# STGHW00054_A2.net
KiCad netlist of a schematic drawn in EAGLE
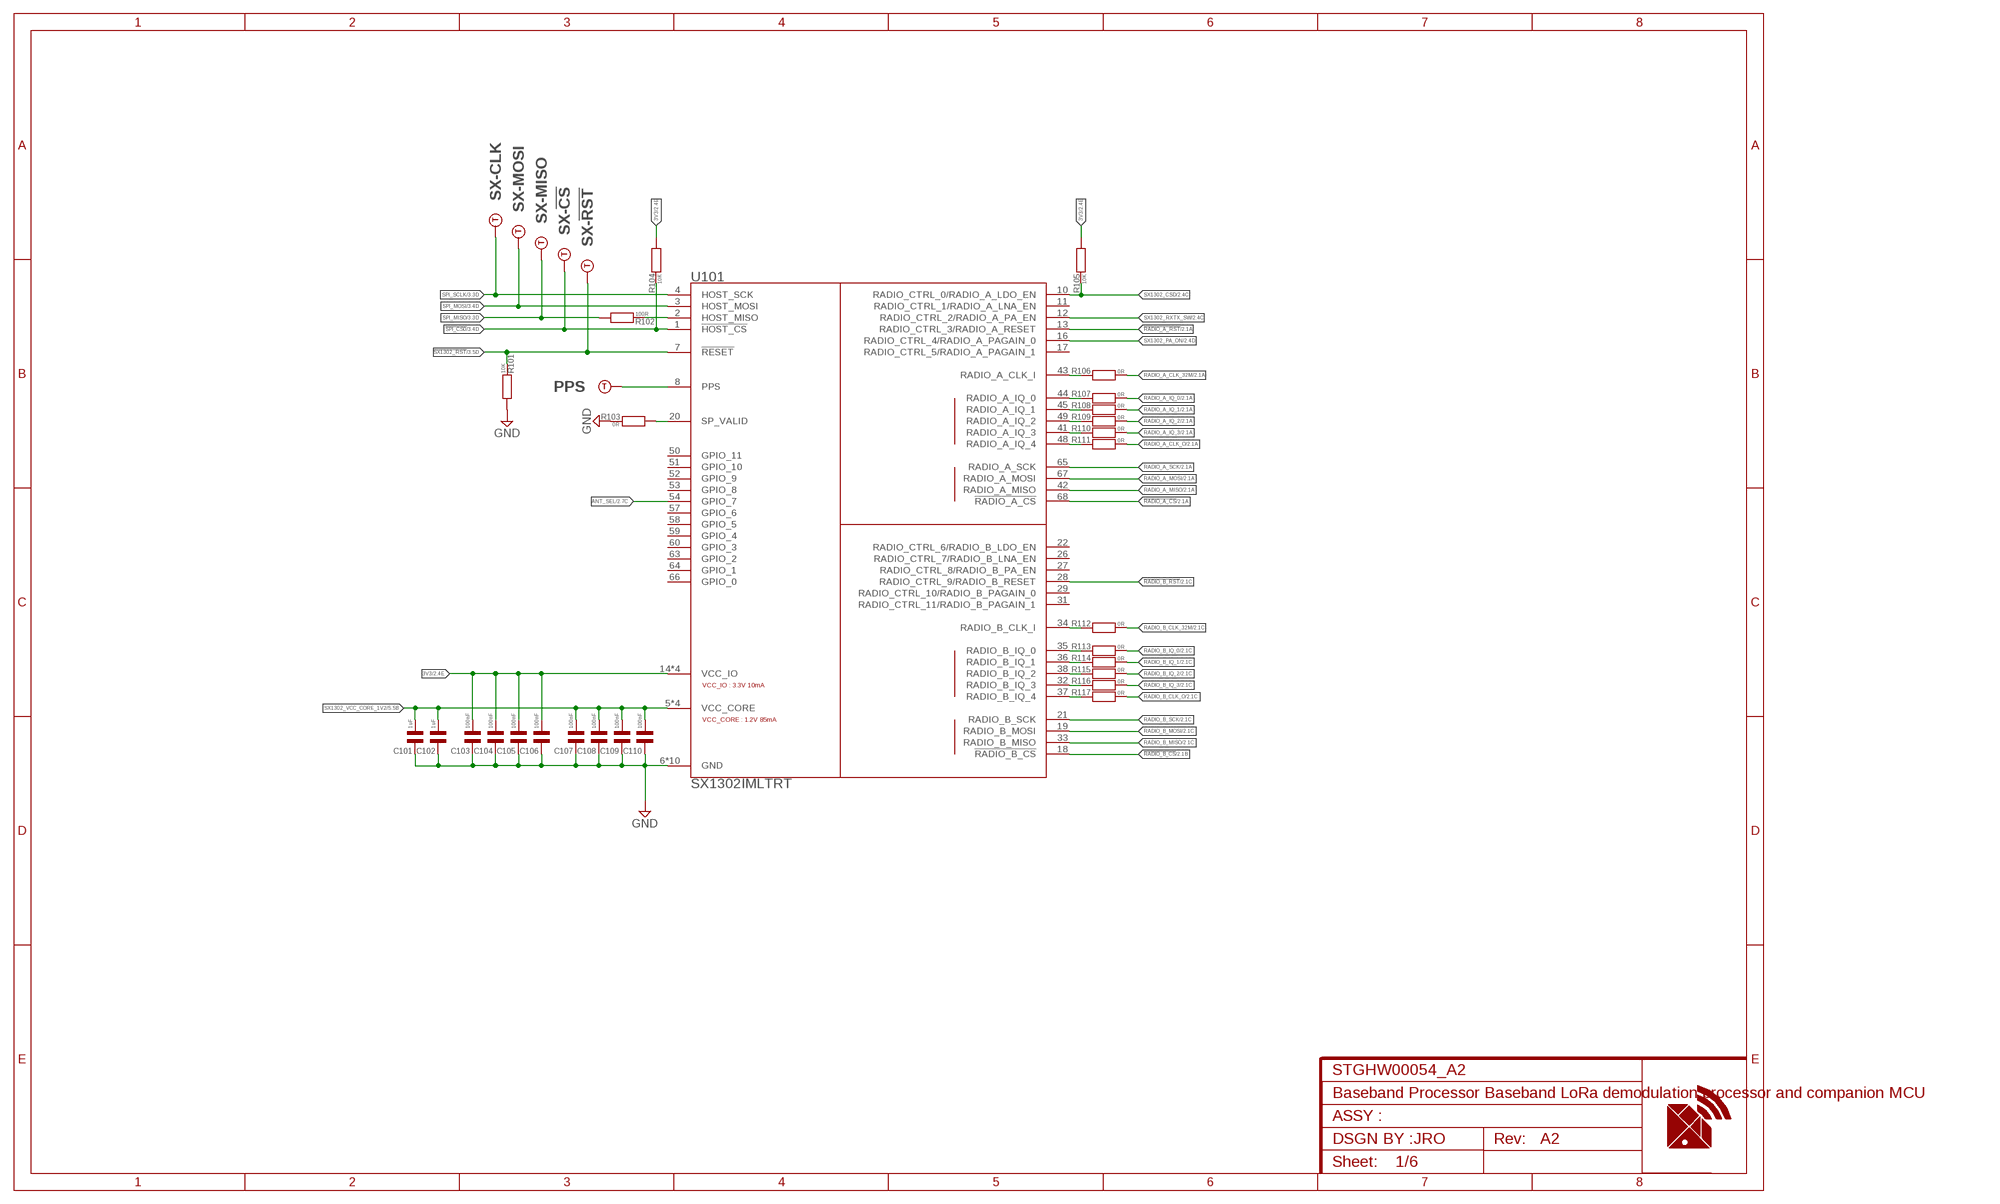
[diagram p0: schematic, sheet 1]
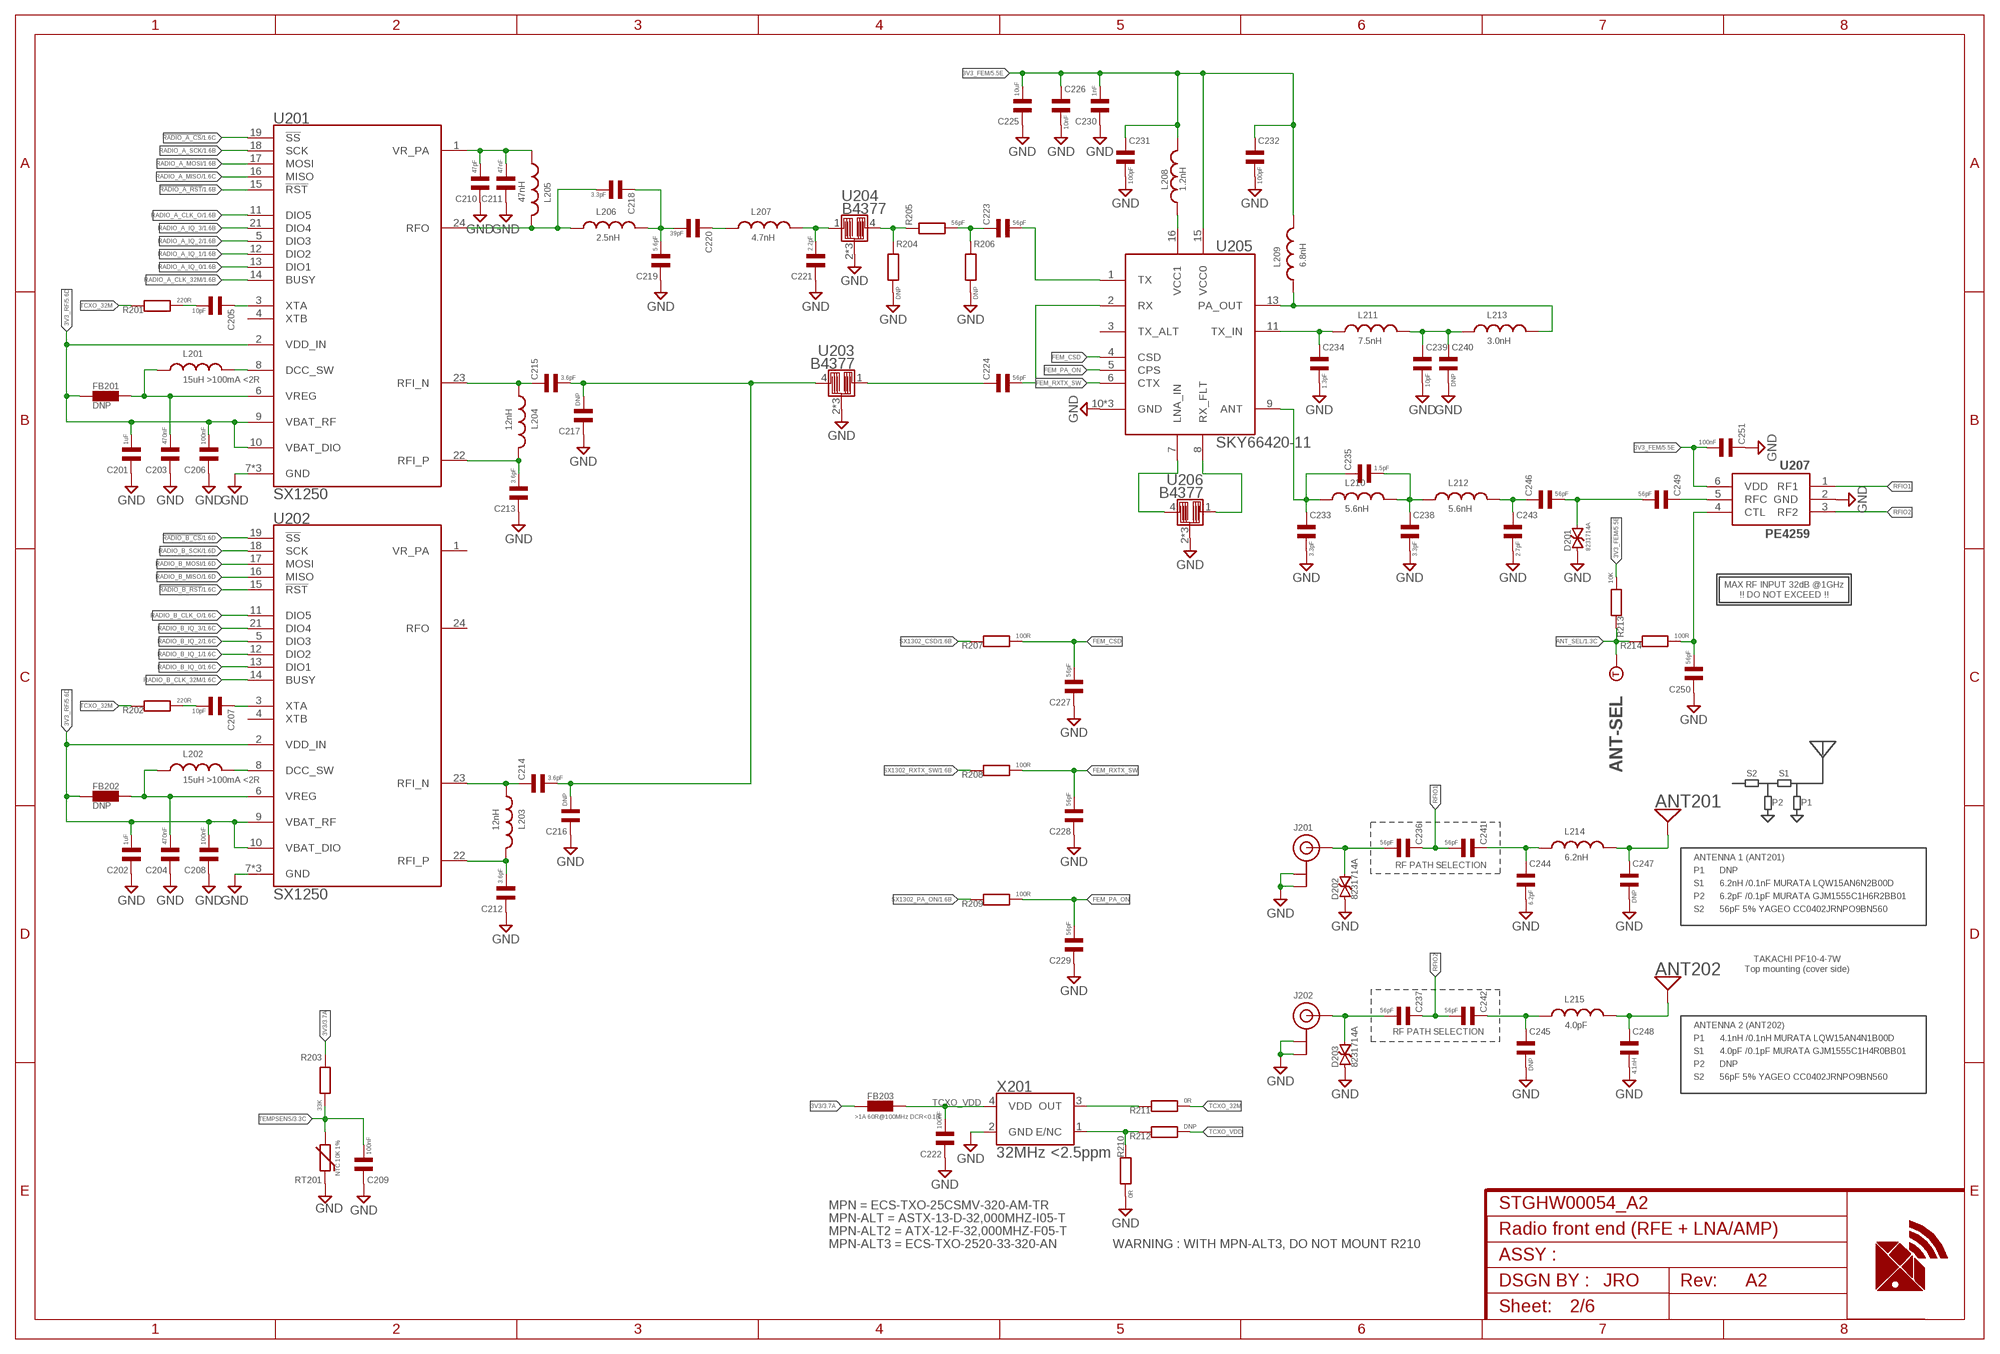
[diagram p1: schematic, sheet 2]
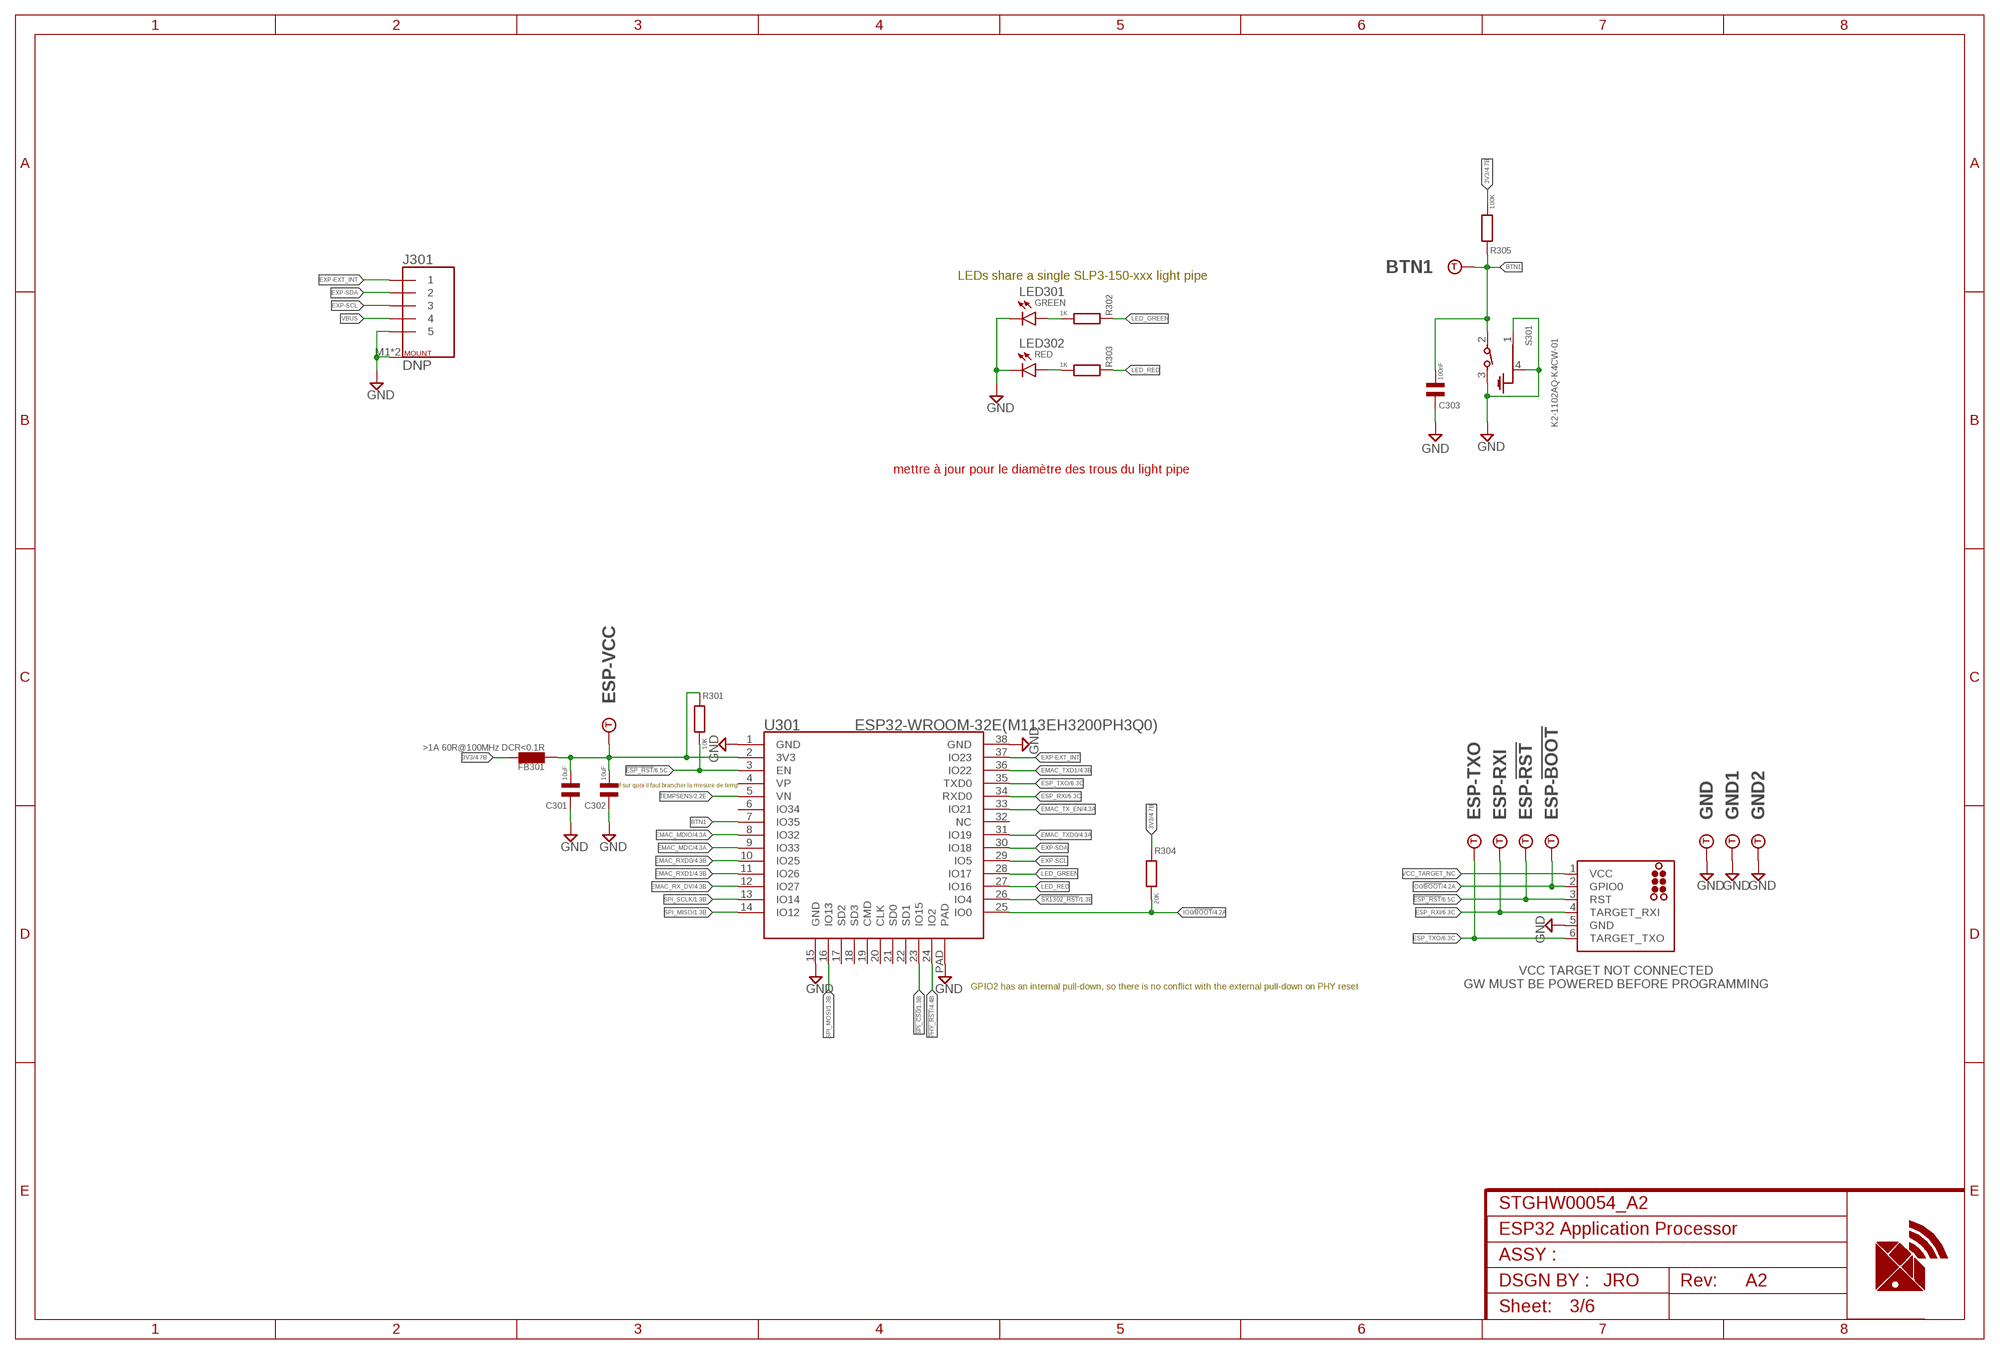
[diagram p2: schematic, sheet 3]
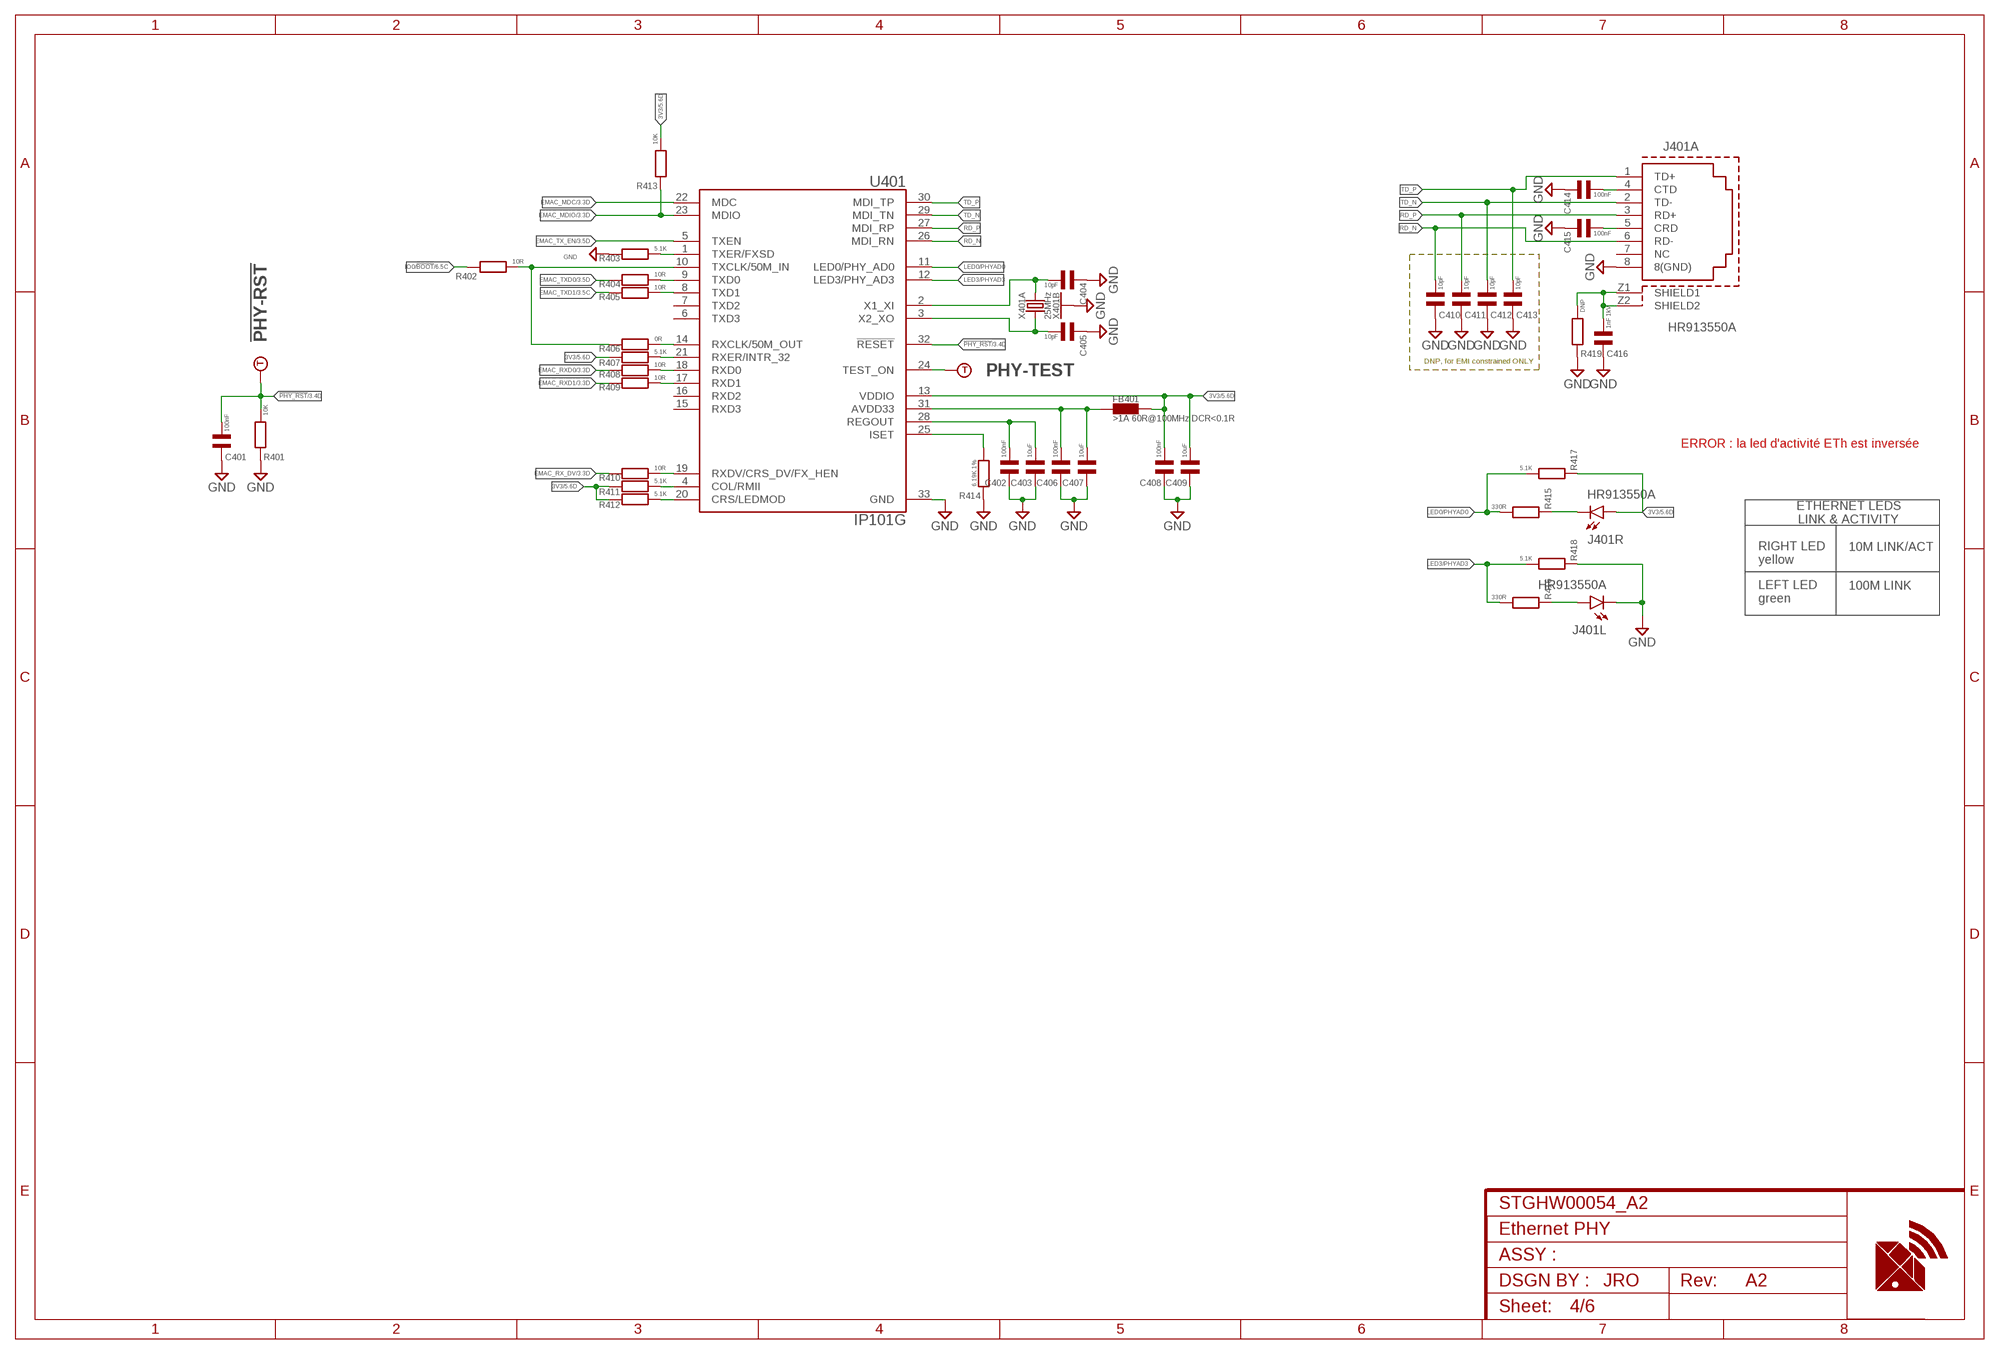
[diagram p3: schematic, sheet 4]
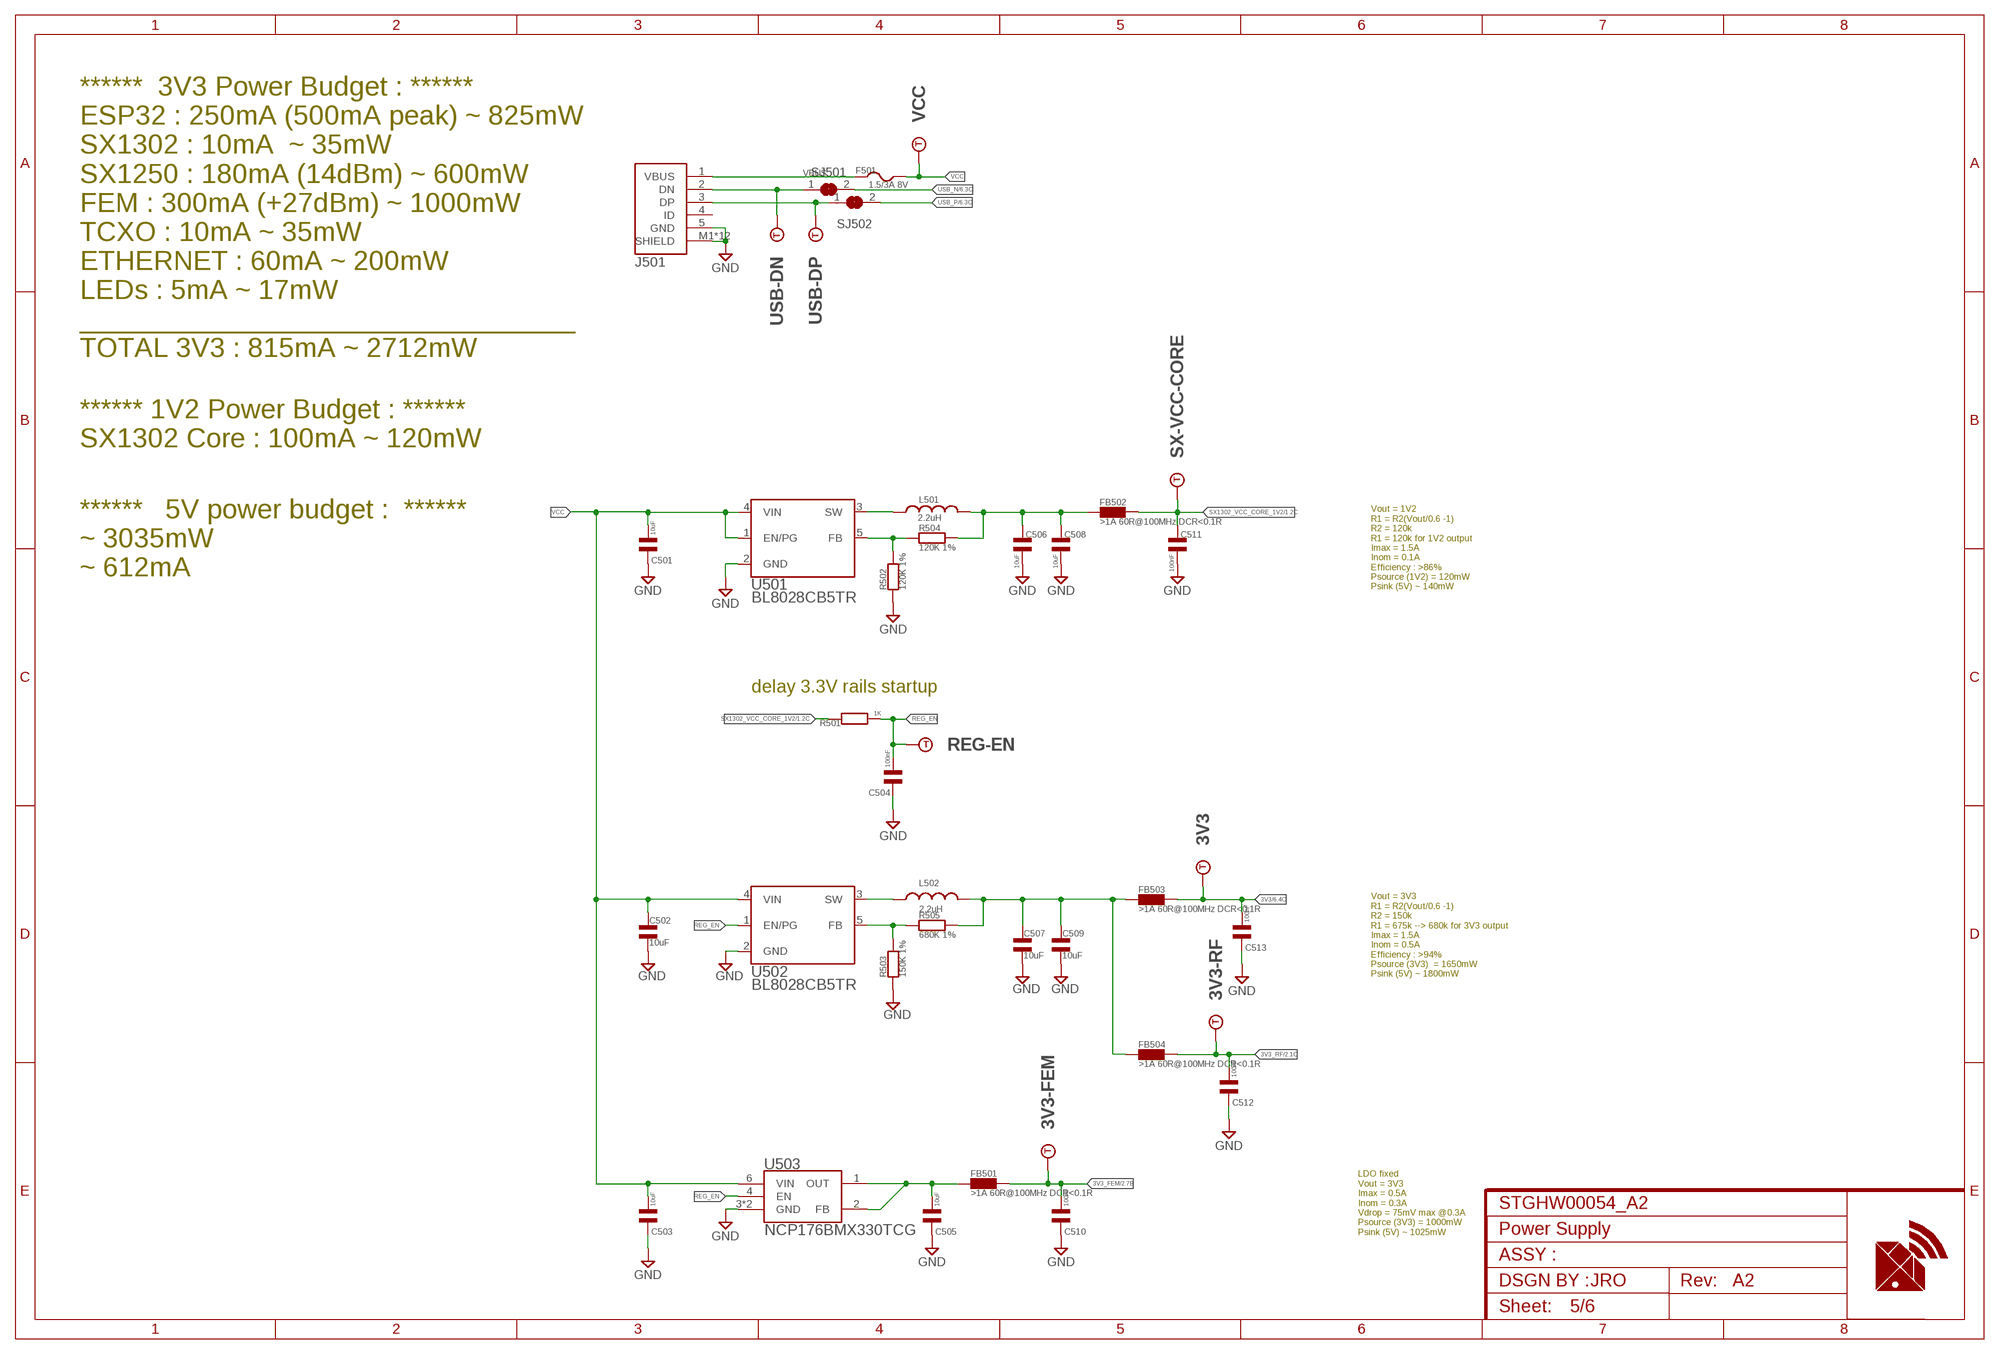
[diagram p4: schematic, sheet 5]
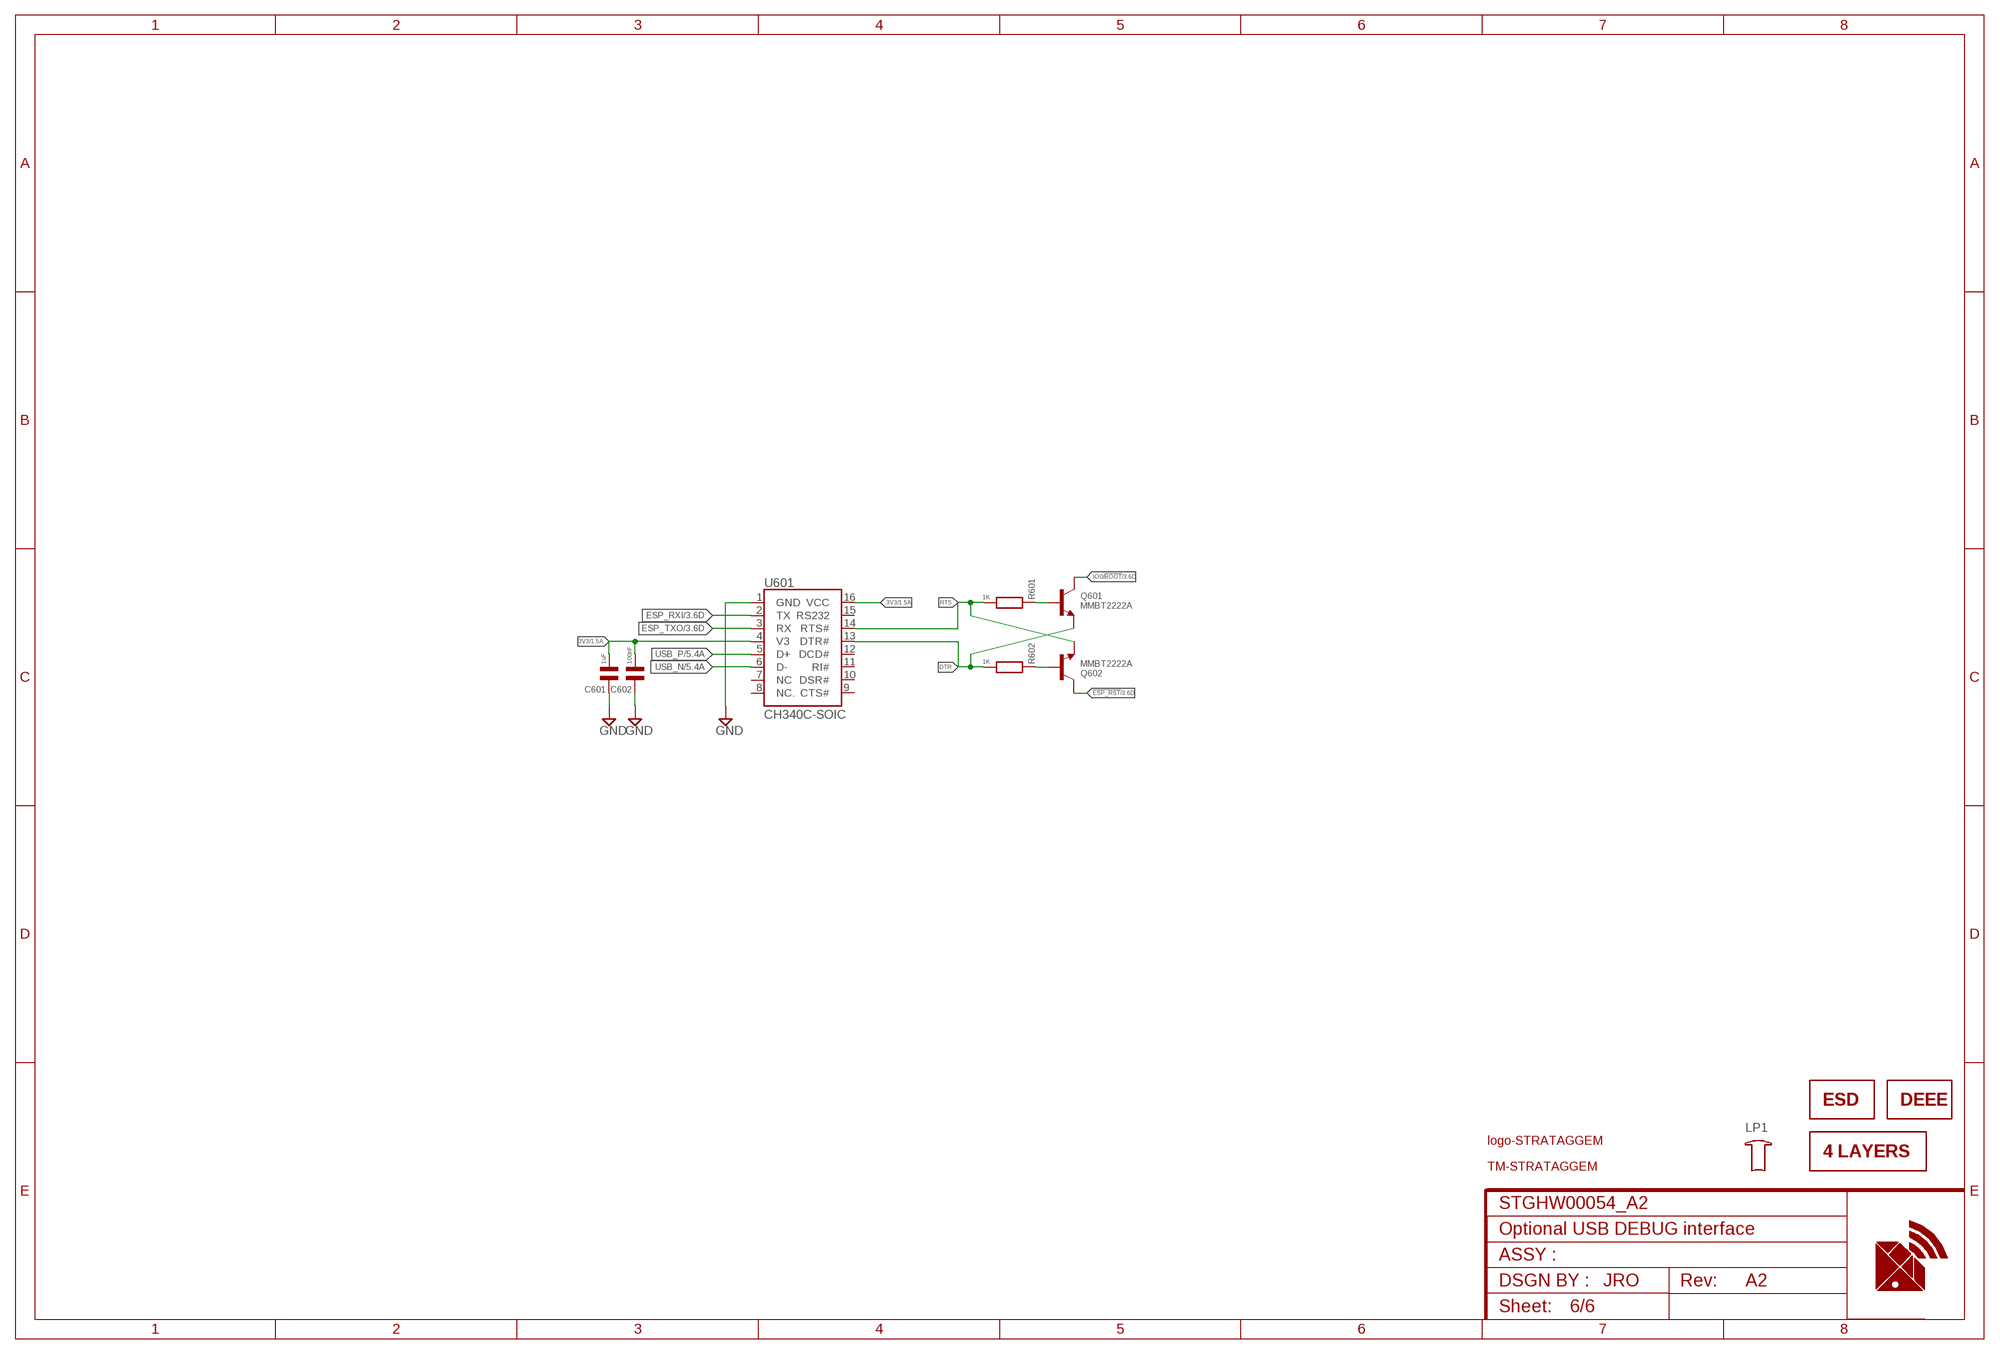
[diagram p5: schematic, sheet 6]

(export (version "E")
  (design (tool "Eeschema 10.0.6"))
  (components
    (comp (ref "C101")
      (value "1uF")
      (footprint "eagle-import:C0402")
      (fields (field (name "MPN") "CL05A105KO5NNNC"))
      (libsource (lib "eagle-import") (part "CAPACITOR-NP-0402"))
    )
    (comp (ref "C102")
      (value "1uF")
      (footprint "eagle-import:C0402")
      (fields (field (name "MPN") "CL05A105KO5NNNC"))
      (libsource (lib "eagle-import") (part "CAPACITOR-NP-0402"))
    )
    (comp (ref "C103")
      (value "100nF")
      (footprint "eagle-import:C0402")
      (fields (field (name "MPN") "CC0402KRX7R7BB104"))
      (libsource (lib "eagle-import") (part "CAPACITOR-NP-0402"))
    )
    (comp (ref "C104")
      (value "100nF")
      (footprint "eagle-import:C0402")
      (fields (field (name "MPN") "CC0402KRX7R7BB104"))
      (libsource (lib "eagle-import") (part "CAPACITOR-NP-0402"))
    )
    (comp (ref "C105")
      (value "100nF")
      (footprint "eagle-import:C0402")
      (fields (field (name "MPN") "CC0402KRX7R7BB104"))
      (libsource (lib "eagle-import") (part "CAPACITOR-NP-0402"))
    )
    (comp (ref "C106")
      (value "100nF")
      (footprint "eagle-import:C0402")
      (fields (field (name "MPN") "CC0402KRX7R7BB104"))
      (libsource (lib "eagle-import") (part "CAPACITOR-NP-0402"))
    )
    (comp (ref "C107")
      (value "100nF")
      (footprint "eagle-import:C0402")
      (fields (field (name "MPN") "CC0402KRX7R7BB104"))
      (libsource (lib "eagle-import") (part "CAPACITOR-NP-0402"))
    )
    (comp (ref "C108")
      (value "100nF")
      (footprint "eagle-import:C0402")
      (fields (field (name "MPN") "CC0402KRX7R7BB104"))
      (libsource (lib "eagle-import") (part "CAPACITOR-NP-0402"))
    )
    (comp (ref "C109")
      (value "100nF")
      (footprint "eagle-import:C0402")
      (fields (field (name "MPN") "CC0402KRX7R7BB104"))
      (libsource (lib "eagle-import") (part "CAPACITOR-NP-0402"))
    )
    (comp (ref "C110")
      (value "100nF")
      (footprint "eagle-import:C0402")
      (fields (field (name "MPN") "CC0402KRX7R7BB104"))
      (libsource (lib "eagle-import") (part "CAPACITOR-NP-0402"))
    )
    (comp (ref "PPS")
      (value "TESPOINT-SMD1.5MM")
      (footprint "eagle-import:TESTPOINT-1.5MM")
      (libsource (lib "eagle-import") (part "TESPOINT-SMD1.5MM"))
    )
    (comp (ref "R101")
      (value "10K")
      (footprint "eagle-import:R0402")
      (fields (field (name "MPN") "RC0402JR-0710KL"))
      (libsource (lib "eagle-import") (part "RESISTOR-0402"))
    )
    (comp (ref "R102")
      (value "100R")
      (footprint "eagle-import:R0402")
      (fields (field (name "MPN") "RC0402JR-07100RL"))
      (libsource (lib "eagle-import") (part "RESISTOR-0402"))
    )
    (comp (ref "R103")
      (value "0R")
      (footprint "eagle-import:R0402")
      (fields (field (name "MPN") "RC0402JR-070RL"))
      (libsource (lib "eagle-import") (part "RESISTOR-0402"))
    )
    (comp (ref "R104")
      (value "10K")
      (footprint "eagle-import:R0402")
      (fields (field (name "MPN") "RC0402JR-0710KL"))
      (libsource (lib "eagle-import") (part "RESISTOR-0402"))
    )
    (comp (ref "R105")
      (value "10K")
      (footprint "eagle-import:R0402")
      (fields (field (name "MPN") "RC0402JR-0710KL"))
      (libsource (lib "eagle-import") (part "RESISTOR-0402"))
    )
    (comp (ref "R106")
      (value "0R")
      (footprint "eagle-import:R0402")
      (fields (field (name "MPN") "RC0402JR-070RL"))
      (libsource (lib "eagle-import") (part "RESISTOR-0402"))
    )
    (comp (ref "R107")
      (value "0R")
      (footprint "eagle-import:R0402")
      (fields (field (name "MPN") "RC0402JR-070RL"))
      (libsource (lib "eagle-import") (part "RESISTOR-0402"))
    )
    (comp (ref "R108")
      (value "0R")
      (footprint "eagle-import:R0402")
      (fields (field (name "MPN") "RC0402JR-070RL"))
      (libsource (lib "eagle-import") (part "RESISTOR-0402"))
    )
    (comp (ref "R109")
      (value "0R")
      (footprint "eagle-import:R0402")
      (fields (field (name "MPN") "RC0402JR-070RL"))
      (libsource (lib "eagle-import") (part "RESISTOR-0402"))
    )
    (comp (ref "R110")
      (value "0R")
      (footprint "eagle-import:R0402")
      (fields (field (name "MPN") "RC0402JR-070RL"))
      (libsource (lib "eagle-import") (part "RESISTOR-0402"))
    )
    (comp (ref "R111")
      (value "0R")
      (footprint "eagle-import:R0402")
      (fields (field (name "MPN") "RC0402JR-070RL"))
      (libsource (lib "eagle-import") (part "RESISTOR-0402"))
    )
    (comp (ref "R112")
      (value "0R")
      (footprint "eagle-import:R0402")
      (fields (field (name "MPN") "RC0402JR-070RL"))
      (libsource (lib "eagle-import") (part "RESISTOR-0402"))
    )
    (comp (ref "R113")
      (value "0R")
      (footprint "eagle-import:R0402")
      (fields (field (name "MPN") "RC0402JR-070RL"))
      (libsource (lib "eagle-import") (part "RESISTOR-0402"))
    )
    (comp (ref "R114")
      (value "0R")
      (footprint "eagle-import:R0402")
      (fields (field (name "MPN") "RC0402JR-070RL"))
      (libsource (lib "eagle-import") (part "RESISTOR-0402"))
    )
    (comp (ref "R115")
      (value "0R")
      (footprint "eagle-import:R0402")
      (fields (field (name "MPN") "RC0402JR-070RL"))
      (libsource (lib "eagle-import") (part "RESISTOR-0402"))
    )
    (comp (ref "R116")
      (value "0R")
      (footprint "eagle-import:R0402")
      (fields (field (name "MPN") "RC0402JR-070RL"))
      (libsource (lib "eagle-import") (part "RESISTOR-0402"))
    )
    (comp (ref "R117")
      (value "0R")
      (footprint "eagle-import:R0402")
      (fields (field (name "MPN") "RC0402JR-070RL"))
      (libsource (lib "eagle-import") (part "RESISTOR-0402"))
    )
    (comp (ref "SX-!CS!")
      (value "TESPOINT-SMD1.5MM")
      (footprint "eagle-import:TESTPOINT-1.5MM")
      (libsource (lib "eagle-import") (part "TESPOINT-SMD1.5MM"))
    )
    (comp (ref "SX-!RST!")
      (value "TESPOINT-SMD1.5MM")
      (footprint "eagle-import:TESTPOINT-1.5MM")
      (libsource (lib "eagle-import") (part "TESPOINT-SMD1.5MM"))
    )
    (comp (ref "SX-CLK")
      (value "TESPOINT-SMD1.5MM")
      (footprint "eagle-import:TESTPOINT-1.5MM")
      (libsource (lib "eagle-import") (part "TESPOINT-SMD1.5MM"))
    )
    (comp (ref "SX-MISO")
      (value "TESPOINT-SMD1.5MM")
      (footprint "eagle-import:TESTPOINT-1.5MM")
      (libsource (lib "eagle-import") (part "TESPOINT-SMD1.5MM"))
    )
    (comp (ref "SX-MOSI")
      (value "TESPOINT-SMD1.5MM")
      (footprint "eagle-import:TESTPOINT-1.5MM")
      (libsource (lib "eagle-import") (part "TESPOINT-SMD1.5MM"))
    )
    (comp (ref "U101")
      (value "SX1302IMLTRT")
      (footprint "eagle-import:QFN35P700X700X80-69T556")
      (fields (field (name "MPN") "SX1302IMLTRT"))
      (libsource (lib "eagle-import") (part "SX1302IMLTRT"))
    )
    (comp (ref "C601")
      (value "1uF")
      (footprint "eagle-import:C0603")
      (fields (field (name "MPN") "CL10B105KP8NNNC"))
      (libsource (lib "eagle-import") (part "CAPACITOR-NP-0603"))
    )
    (comp (ref "C602")
      (value "100nF")
      (footprint "eagle-import:C0603")
      (fields (field (name "MPN") "CL10B104KO8NNNC"))
      (libsource (lib "eagle-import") (part "CAPACITOR-NP-0603"))
    )
    (comp (ref "LOGO1")
      (value "LOGO_STRATAGGEM_SILK_5")
      (footprint "eagle-import:STG_LOGO_1L_SILK_5")
      (libsource (lib "eagle-import") (part "LOGO_STRATAGGEM_SILK_5"))
    )
    (comp (ref "LOGO601")
      (value "ESD_LOGO-SILK-TOP-5")
      (footprint "eagle-import:ESD_TOP_5MM")
      (libsource (lib "eagle-import") (part "ESD_LOGO-SILK-TOP-5"))
    )
    (comp (ref "LOGO602")
      (value "DEEE_LOGO-SILK-TOP-5")
      (footprint "eagle-import:DEEE_MUELLTONNE_TOP_5MM")
      (libsource (lib "eagle-import") (part "DEEE_LOGO-SILK-TOP-5"))
    )
    (comp (ref "LP1")
      (value "SLP3-150-250-F")
      (footprint "eagle-import:SLP3-150-250-F")
      (libsource (lib "eagle-import") (part "SLP3-150-250-F"))
    )
    (comp (ref "Q601")
      (value "MMBT2222A")
      (footprint "eagle-import:SOT23-WIDE")
      (fields (field (name "MPN") "MMBT2222A"))
      (libsource (lib "eagle-import") (part "TRANSISTOR_NPNWIDE"))
    )
    (comp (ref "Q602")
      (value "MMBT2222A")
      (footprint "eagle-import:SOT23-WIDE")
      (fields (field (name "MPN") "MMBT2222A"))
      (libsource (lib "eagle-import") (part "TRANSISTOR_NPNWIDE"))
    )
    (comp (ref "R601")
      (value "1K")
      (footprint "eagle-import:R0603")
      (fields (field (name "MPN") "WR06X1001FTL"))
      (libsource (lib "eagle-import") (part "RESISTOR-0603"))
    )
    (comp (ref "R602")
      (value "1K")
      (footprint "eagle-import:R0603")
      (fields (field (name "MPN") "WR06X1001FTL"))
      (libsource (lib "eagle-import") (part "RESISTOR-0603"))
    )
    (comp (ref "SPEC1")
      (value "LAYER_4")
      (footprint "eagle-import:4LAYER")
      (libsource (lib "eagle-import") (part "LAYER_4"))
    )
    (comp (ref "TM1")
      (value "TM_STRATAGGEM_SILK_20")
      (footprint "eagle-import:STG_MARK_SILK_TOP_20MM")
      (libsource (lib "eagle-import") (part "TM_STRATAGGEM_SILK_20"))
    )
    (comp (ref "U601")
      (value "CH340C-SOIC")
      (footprint "eagle-import:SOIC127P600X175-16")
      (libsource (lib "eagle-import") (part "CH340C-SOIC"))
    )
    (comp (ref "ANT-SEL")
      (value "TESPOINT-SMD1.5MM")
      (footprint "eagle-import:TESTPOINT-1.5MM")
      (libsource (lib "eagle-import") (part "TESPOINT-SMD1.5MM"))
    )
    (comp (ref "ANT201")
      (value "MLA-DN038")
      (footprint "eagle-import:DN038")
      (libsource (lib "eagle-import") (part "MLA-DN038"))
    )
    (comp (ref "ANT202")
      (value "MLA-DN038-MIRROR")
      (footprint "eagle-import:DN038_MIRROR")
      (libsource (lib "eagle-import") (part "MLA-DN038-MIRROR"))
    )
    (comp (ref "C201")
      (value "1uF")
      (footprint "eagle-import:C0402")
      (fields (field (name "MPN") "CL05A105KO5NNNC"))
      (libsource (lib "eagle-import") (part "CAPACITOR-NP-0402"))
    )
    (comp (ref "C202")
      (value "1uF")
      (footprint "eagle-import:C0402")
      (fields (field (name "MPN") "CL05A105KO5NNNC"))
      (libsource (lib "eagle-import") (part "CAPACITOR-NP-0402"))
    )
    (comp (ref "C203")
      (value "470nF")
      (footprint "eagle-import:C0603")
      (fields (field (name "MPN") "CL10B474KO8NNNC"))
      (libsource (lib "eagle-import") (part "CAPACITOR-NP-0603"))
    )
    (comp (ref "C204")
      (value "470nF")
      (footprint "eagle-import:C0603")
      (fields (field (name "MPN") "CL10B474KO8NNNC"))
      (libsource (lib "eagle-import") (part "CAPACITOR-NP-0603"))
    )
    (comp (ref "C205")
      (value "10pF")
      (footprint "eagle-import:C0402")
      (fields (field (name "MPN") "CC0402JRNPO9BN100"))
      (libsource (lib "eagle-import") (part "CAPACITOR-NP-0402"))
    )
    (comp (ref "C206")
      (value "100nF")
      (footprint "eagle-import:C0402")
      (fields (field (name "MPN") "CC0402KRX7R7BB104"))
      (libsource (lib "eagle-import") (part "CAPACITOR-NP-0402"))
    )
    (comp (ref "C207")
      (value "10pF")
      (footprint "eagle-import:C0402")
      (fields (field (name "MPN") "CC0402JRNPO9BN100"))
      (libsource (lib "eagle-import") (part "CAPACITOR-NP-0402"))
    )
    (comp (ref "C208")
      (value "100nF")
      (footprint "eagle-import:C0402")
      (fields (field (name "MPN") "CC0402KRX7R7BB104"))
      (libsource (lib "eagle-import") (part "CAPACITOR-NP-0402"))
    )
    (comp (ref "C209")
      (value "100nF")
      (footprint "eagle-import:C0402")
      (fields (field (name "MPN") "CC0402KRX7R7BB104"))
      (libsource (lib "eagle-import") (part "CAPACITOR-NP-0402"))
    )
    (comp (ref "C210")
      (value "47pF")
      (footprint "eagle-import:C0402")
      (fields (field (name "MPN") "0402N470F500CT"))
      (libsource (lib "eagle-import") (part "CAPACITOR-NP-0402"))
    )
    (comp (ref "C211")
      (value "47nF")
      (footprint "eagle-import:C0402")
      (fields (field (name "MPN") "0402B473K250CT"))
      (libsource (lib "eagle-import") (part "CAPACITOR-NP-0402"))
    )
    (comp (ref "C212")
      (value "3.6pF")
      (footprint "eagle-import:C0402")
      (fields (field (name "MPN") "GJM1555C1H3R6BB01D"))
      (libsource (lib "eagle-import") (part "CAPACITOR-NP-0402"))
    )
    (comp (ref "C213")
      (value "3.6pF")
      (footprint "eagle-import:C0402")
      (fields (field (name "MPN") "GJM1555C1H3R6BB01D"))
      (libsource (lib "eagle-import") (part "CAPACITOR-NP-0402"))
    )
    (comp (ref "C214")
      (value "3.6pF")
      (footprint "eagle-import:C0402")
      (fields (field (name "MPN") "GJM1555C1H3R6BB01D"))
      (libsource (lib "eagle-import") (part "CAPACITOR-NP-0402"))
    )
    (comp (ref "C215")
      (value "3.6pF")
      (footprint "eagle-import:C0402")
      (fields (field (name "MPN") "GJM1555C1H3R6BB01D"))
      (libsource (lib "eagle-import") (part "CAPACITOR-NP-0402"))
    )
    (comp (ref "C216")
      (value "DNP")
      (footprint "eagle-import:C0402")
      (libsource (lib "eagle-import") (part "CAPACITOR-NP-0402"))
    )
    (comp (ref "C217")
      (value "DNP")
      (footprint "eagle-import:C0402")
      (libsource (lib "eagle-import") (part "CAPACITOR-NP-0402"))
    )
    (comp (ref "C218")
      (value "3.3pF")
      (footprint "eagle-import:C0402")
      (fields (field (name "MPN") "GJM1555C1H3R3BB01D"))
      (libsource (lib "eagle-import") (part "CAPACITOR-NP-0402"))
    )
    (comp (ref "C219")
      (value "5.6pF")
      (footprint "eagle-import:C0402")
      (fields (field (name "MPN") "GJM1555C1H5R6BB01D"))
      (libsource (lib "eagle-import") (part "CAPACITOR-NP-0402"))
    )
    (comp (ref "C220")
      (value "39pF")
      (footprint "eagle-import:C0402")
      (fields (field (name "MPN") "GJM1555C1H390FB01D"))
      (libsource (lib "eagle-import") (part "CAPACITOR-NP-0402"))
    )
    (comp (ref "C221")
      (value "2.2pF")
      (footprint "eagle-import:C0402")
      (fields (field (name "MPN") "GJM1555C1H2R2BB01D"))
      (libsource (lib "eagle-import") (part "CAPACITOR-NP-0402"))
    )
    (comp (ref "C222")
      (value "100nF")
      (footprint "eagle-import:C0402")
      (fields (field (name "MPN") "CC0402KRX7R7BB104"))
      (libsource (lib "eagle-import") (part "CAPACITOR-NP-0402"))
    )
    (comp (ref "C223")
      (value "56pF")
      (footprint "eagle-import:C0402")
      (fields (field (name "MPN") "CC0402JRNPO9BN560"))
      (libsource (lib "eagle-import") (part "CAPACITOR-NP-0402"))
    )
    (comp (ref "C224")
      (value "56pF")
      (footprint "eagle-import:C0402")
      (fields (field (name "MPN") "CC0402JRNPO9BN560"))
      (libsource (lib "eagle-import") (part "CAPACITOR-NP-0402"))
    )
    (comp (ref "C225")
      (value "10uF")
      (footprint "eagle-import:C0603")
      (fields (field (name "MPN") "CL10A106KP8NNNC"))
      (libsource (lib "eagle-import") (part "CAPACITOR-NP-0603"))
    )
    (comp (ref "C226")
      (value "10nF")
      (footprint "eagle-import:C0402")
      (fields (field (name "MPN") "CC0402KRX7R9BB103"))
      (libsource (lib "eagle-import") (part "CAPACITOR-NP-0402"))
    )
    (comp (ref "C227")
      (value "56pF")
      (footprint "eagle-import:C0402")
      (fields (field (name "MPN") "CC0402JRNPO9BN560"))
      (libsource (lib "eagle-import") (part "CAPACITOR-NP-0402"))
    )
    (comp (ref "C228")
      (value "56pF")
      (footprint "eagle-import:C0402")
      (fields (field (name "MPN") "CC0402JRNPO9BN560"))
      (libsource (lib "eagle-import") (part "CAPACITOR-NP-0402"))
    )
    (comp (ref "C229")
      (value "56pF")
      (footprint "eagle-import:C0402")
      (fields (field (name "MPN") "CC0402JRNPO9BN560"))
      (libsource (lib "eagle-import") (part "CAPACITOR-NP-0402"))
    )
    (comp (ref "C230")
      (value "1nF")
      (footprint "eagle-import:C0402")
      (fields (field (name "MPN") "CC0402KRX7R9BB102"))
      (libsource (lib "eagle-import") (part "CAPACITOR-NP-0402"))
    )
    (comp (ref "C231")
      (value "100pF")
      (footprint "eagle-import:C0402")
      (fields (field (name "MPN") "CC0402JRNPO9BN101"))
      (libsource (lib "eagle-import") (part "CAPACITOR-NP-0402"))
    )
    (comp (ref "C232")
      (value "100pF")
      (footprint "eagle-import:C0402")
      (fields (field (name "MPN") "CC0402JRNPO9BN101"))
      (libsource (lib "eagle-import") (part "CAPACITOR-NP-0402"))
    )
    (comp (ref "C233")
      (value "3.3pF")
      (footprint "eagle-import:C0402")
      (fields (field (name "MPN") "GJM1555C1H3R3BB01D"))
      (libsource (lib "eagle-import") (part "CAPACITOR-NP-0402"))
    )
    (comp (ref "C234")
      (value "1.3pF")
      (footprint "eagle-import:C0402")
      (fields (field (name "MPN") "GJM1555C1H1R3BB01D"))
      (libsource (lib "eagle-import") (part "CAPACITOR-NP-0402"))
    )
    (comp (ref "C235")
      (value "1.5pF")
      (footprint "eagle-import:C0402")
      (fields (field (name "MPN") "GJM1555C1H1R5BB01D"))
      (libsource (lib "eagle-import") (part "CAPACITOR-NP-0402"))
    )
    (comp (ref "C236")
      (value "56pF")
      (footprint "eagle-import:C0402")
      (fields (field (name "MPN") "CC0402JRNPO9BN560"))
      (libsource (lib "eagle-import") (part "CAPACITOR-NP-0402"))
    )
    (comp (ref "C237")
      (value "56pF")
      (footprint "eagle-import:C0402")
      (fields (field (name "MPN") "CC0402JRNPO9BN560"))
      (libsource (lib "eagle-import") (part "CAPACITOR-NP-0402"))
    )
    (comp (ref "C238")
      (value "3.3pF")
      (footprint "eagle-import:C0402")
      (fields (field (name "MPN") "GJM1555C1H3R3BB01D"))
      (libsource (lib "eagle-import") (part "CAPACITOR-NP-0402"))
    )
    (comp (ref "C239")
      (value "10pF")
      (footprint "eagle-import:C0402")
      (fields (field (name "MPN") "CC0402JRNPO9BN100"))
      (libsource (lib "eagle-import") (part "CAPACITOR-NP-0402"))
    )
    (comp (ref "C240")
      (value "DNP")
      (footprint "eagle-import:C0402")
      (libsource (lib "eagle-import") (part "CAPACITOR-NP-0402"))
    )
    (comp (ref "C241")
      (value "56pF")
      (footprint "eagle-import:C0402")
      (fields (field (name "MPN") "CC0402JRNPO9BN560"))
      (libsource (lib "eagle-import") (part "CAPACITOR-NP-0402"))
    )
    (comp (ref "C242")
      (value "56pF")
      (footprint "eagle-import:C0402")
      (fields (field (name "MPN") "CC0402JRNPO9BN560"))
      (libsource (lib "eagle-import") (part "CAPACITOR-NP-0402"))
    )
    (comp (ref "C243")
      (value "2.7pF")
      (footprint "eagle-import:C0402")
      (fields (field (name "MPN") "GJM1555C1H2R7BB01D"))
      (libsource (lib "eagle-import") (part "CAPACITOR-NP-0402"))
    )
    (comp (ref "C244")
      (value "6.2pF")
      (footprint "eagle-import:C0402")
      (fields (field (name "MPN") "GJM1555C1H6R2BB01D"))
      (libsource (lib "eagle-import") (part "CAPACITOR-NP-0402"))
    )
    (comp (ref "C245")
      (value "DNP")
      (footprint "eagle-import:C0402")
      (libsource (lib "eagle-import") (part "CAPACITOR-NP-0402"))
    )
    (comp (ref "C246")
      (value "56pF")
      (footprint "eagle-import:C0402")
      (fields (field (name "MPN") "CC0402JRNPO9BN560"))
      (libsource (lib "eagle-import") (part "CAPACITOR-NP-0402"))
    )
    (comp (ref "C247")
      (value "DNP")
      (footprint "eagle-import:C0402")
      (libsource (lib "eagle-import") (part "CAPACITOR-NP-0402"))
    )
    (comp (ref "C248")
      (value "4.1nH")
      (footprint "eagle-import:C0402")
      (fields (field (name "MPN") "LQW15AN4N1B00D"))
      (libsource (lib "eagle-import") (part "CAPACITOR-NP-0402"))
    )
    (comp (ref "C249")
      (value "56pF")
      (footprint "eagle-import:C0402")
      (fields (field (name "MPN") "CC0402JRNPO9BN560"))
      (libsource (lib "eagle-import") (part "CAPACITOR-NP-0402"))
    )
    (comp (ref "C250")
      (value "56pF")
      (footprint "eagle-import:C0402")
      (fields (field (name "MPN") "CC0402JRNPO9BN560"))
      (libsource (lib "eagle-import") (part "CAPACITOR-NP-0402"))
    )
    (comp (ref "C251")
      (value "100nF")
      (footprint "eagle-import:C0402")
      (fields (field (name "MPN") "CC0402KRX7R7BB104"))
      (libsource (lib "eagle-import") (part "CAPACITOR-NP-0402"))
    )
    (comp (ref "D201")
      (value "8231714A")
      (footprint "eagle-import:TVS0402")
      (libsource (lib "eagle-import") (part "TVS-0402"))
    )
    (comp (ref "D202")
      (value "8231714A")
      (footprint "eagle-import:TVS0402")
      (libsource (lib "eagle-import") (part "TVS-0402"))
    )
    (comp (ref "D203")
      (value "8231714A")
      (footprint "eagle-import:TVS0402")
      (libsource (lib "eagle-import") (part "TVS-0402"))
    )
    (comp (ref "FB201")
      (value "DNP")
      (footprint "eagle-import:FB0402")
      (fields (field (name "MPN") "BLM15PD600SN1D"))
      (libsource (lib "eagle-import") (part "FERRITE-0402"))
    )
    (comp (ref "FB202")
      (value "DNP")
      (footprint "eagle-import:FB0402")
      (fields (field (name "MPN") "BLM15PD600SN1D"))
      (libsource (lib "eagle-import") (part "FERRITE-0402"))
    )
    (comp (ref "FB203")
      (value ">1A 60R@100MHz DCR<0.1R")
      (footprint "eagle-import:FB0402")
      (fields (field (name "MPN") "BLM15PD600SN1D"))
      (libsource (lib "eagle-import") (part "FERRITE-0402"))
    )
    (comp (ref "J201")
      (value "DNP")
      (footprint "eagle-import:U.FL_AMPHENOL_RF_A-1JB")
      (fields (field (name "MPN") "U.FL-R-SMT-1(80)"))
      (libsource (lib "eagle-import") (part "UFL_CONNECTOR_AMPHENOL_A-1JB"))
    )
    (comp (ref "J202")
      (value "DNP")
      (footprint "eagle-import:U.FL_AMPHENOL_RF_A-1JB")
      (fields (field (name "MPN") "U.FL-R-SMT-1(80)"))
      (libsource (lib "eagle-import") (part "UFL_CONNECTOR_AMPHENOL_A-1JB"))
    )
    (comp (ref "L201")
      (value "15uH >100mA <2R")
      (footprint "eagle-import:L0805")
      (fields (field (name "MPN") "MLZ2012M150WT000"))
      (libsource (lib "eagle-import") (part "INDUCTOR-0805"))
    )
    (comp (ref "L202")
      (value "15uH >100mA <2R")
      (footprint "eagle-import:L0805")
      (fields (field (name "MPN") "MLZ2012M150WT000"))
      (libsource (lib "eagle-import") (part "INDUCTOR-0805"))
    )
    (comp (ref "L203")
      (value "12nH")
      (footprint "eagle-import:L0402")
      (fields (field (name "MPN") "LQW15AN12NG00D"))
      (libsource (lib "eagle-import") (part "INDUCTOR-0402"))
    )
    (comp (ref "L204")
      (value "12nH")
      (footprint "eagle-import:L0402")
      (fields (field (name "MPN") "LQW15AN12NG00D"))
      (libsource (lib "eagle-import") (part "INDUCTOR-0402"))
    )
    (comp (ref "L205")
      (value "47nH")
      (footprint "eagle-import:L0402")
      (fields (field (name "MPN") "LQW15AN47NG00D"))
      (libsource (lib "eagle-import") (part "INDUCTOR-0402"))
    )
    (comp (ref "L206")
      (value "2.5nH")
      (footprint "eagle-import:L0402")
      (fields (field (name "MPN") "LQW15AN2N5C00D"))
      (libsource (lib "eagle-import") (part "INDUCTOR-0402"))
    )
    (comp (ref "L207")
      (value "4.7nH")
      (footprint "eagle-import:L0402")
      (fields (field (name "MPN") "LQW15AN4N7C00D"))
      (libsource (lib "eagle-import") (part "INDUCTOR-0402"))
    )
    (comp (ref "L208")
      (value "1.2nH")
      (footprint "eagle-import:L0402")
      (fields (field (name "MPN") "LQG15HS1N2B02D"))
      (libsource (lib "eagle-import") (part "INDUCTOR-0402"))
    )
    (comp (ref "L209")
      (value "6.8nH")
      (footprint "eagle-import:L0402")
      (fields (field (name "MPN") "LQW15AN6N8G80D"))
      (libsource (lib "eagle-import") (part "INDUCTOR-0402"))
    )
    (comp (ref "L210")
      (value "5.6nH")
      (footprint "eagle-import:L0402")
      (fields (field (name "MPN") "LQW15AN5N6C10D"))
      (libsource (lib "eagle-import") (part "INDUCTOR-0402"))
    )
    (comp (ref "L211")
      (value "7.5nH")
      (footprint "eagle-import:L0402")
      (fields (field (name "MPN") "LQW15AN7N5G00D"))
      (libsource (lib "eagle-import") (part "INDUCTOR-0402"))
    )
    (comp (ref "L212")
      (value "5.6nH")
      (footprint "eagle-import:L0402")
      (fields (field (name "MPN") "LQW15AN5N6C10D"))
      (libsource (lib "eagle-import") (part "INDUCTOR-0402"))
    )
    (comp (ref "L213")
      (value "3.0nH")
      (footprint "eagle-import:L0402")
      (fields (field (name "MPN") "LQW15AN3N0C80D"))
      (libsource (lib "eagle-import") (part "INDUCTOR-0402"))
    )
    (comp (ref "L214")
      (value "6.2nH")
      (footprint "eagle-import:L0402")
      (fields (field (name "MPN") "LQW15AN6N2B00D"))
      (libsource (lib "eagle-import") (part "INDUCTOR-0402"))
    )
    (comp (ref "L215")
      (value "4.0pF")
      (footprint "eagle-import:L0402")
      (fields (field (name "MPN") "GJM1555C1H4R0BB01D"))
      (libsource (lib "eagle-import") (part "INDUCTOR-0402"))
    )
    (comp (ref "R201")
      (value "220R")
      (footprint "eagle-import:R0402")
      (fields (field (name "MPN") "0402WGF2200TCE"))
      (libsource (lib "eagle-import") (part "RESISTOR-0402"))
    )
    (comp (ref "R202")
      (value "220R")
      (footprint "eagle-import:R0402")
      (fields (field (name "MPN") "0402WGF2200TCE"))
      (libsource (lib "eagle-import") (part "RESISTOR-0402"))
    )
    (comp (ref "R203")
      (value "33K")
      (footprint "eagle-import:R0402")
      (fields (field (name "MPN") "RC0402JR-0710KL"))
      (libsource (lib "eagle-import") (part "RESISTOR-0402"))
    )
    (comp (ref "R204")
      (value "DNP")
      (footprint "eagle-import:R0402")
      (libsource (lib "eagle-import") (part "RESISTOR-0402"))
    )
    (comp (ref "R205")
      (value "56pF")
      (footprint "eagle-import:R0402")
      (fields (field (name "MPN") "CC0402JRNPO9BN560"))
      (libsource (lib "eagle-import") (part "RESISTOR-0402"))
    )
    (comp (ref "R206")
      (value "DNP")
      (footprint "eagle-import:R0402")
      (libsource (lib "eagle-import") (part "RESISTOR-0402"))
    )
    (comp (ref "R207")
      (value "100R")
      (footprint "eagle-import:R0402")
      (fields (field (name "MPN") "RC0402JR-07100RL"))
      (libsource (lib "eagle-import") (part "RESISTOR-0402"))
    )
    (comp (ref "R208")
      (value "100R")
      (footprint "eagle-import:R0402")
      (fields (field (name "MPN") "RC0402JR-07100RL"))
      (libsource (lib "eagle-import") (part "RESISTOR-0402"))
    )
    (comp (ref "R209")
      (value "100R")
      (footprint "eagle-import:R0402")
      (fields (field (name "MPN") "RC0402JR-07100RL"))
      (libsource (lib "eagle-import") (part "RESISTOR-0402"))
    )
    (comp (ref "R210")
      (value "0R")
      (footprint "eagle-import:R0402")
      (fields (field (name "MPN") "RC0402JR-070RL"))
      (libsource (lib "eagle-import") (part "RESISTOR-0402"))
    )
    (comp (ref "R211")
      (value "0R")
      (footprint "eagle-import:R0402")
      (fields (field (name "MPN") "RC0402JR-070RL"))
      (libsource (lib "eagle-import") (part "RESISTOR-0402"))
    )
    (comp (ref "R212")
      (value "DNP")
      (footprint "eagle-import:R0402")
      (fields (field (name "MPN") "RC0402JR-070RL"))
      (libsource (lib "eagle-import") (part "RESISTOR-0402"))
    )
    (comp (ref "R213")
      (value "10K")
      (footprint "eagle-import:R0402")
      (fields (field (name "MPN") "RC0402JR-0710KL"))
      (libsource (lib "eagle-import") (part "RESISTOR-0402"))
    )
    (comp (ref "R214")
      (value "100R")
      (footprint "eagle-import:R0402")
      (fields (field (name "MPN") "RC0402JR-07100RL"))
      (libsource (lib "eagle-import") (part "RESISTOR-0402"))
    )
    (comp (ref "RT201")
      (value "NTC 10K 1%")
      (footprint "eagle-import:R0402")
      (fields (field (name "MPN") "NCP15XH103F03RC"))
      (libsource (lib "eagle-import") (part "NTC-THERMISTOR-0402"))
    )
    (comp (ref "U201")
      (value "SX1250")
      (footprint "eagle-import:QFN50P400X400X100-25T270")
      (fields (field (name "MPN") "SX1250IMLTRT"))
      (libsource (lib "eagle-import") (part "SX1250"))
    )
    (comp (ref "U202")
      (value "SX1250")
      (footprint "eagle-import:QFN50P400X400X100-25T270")
      (fields (field (name "MPN") "SX1250IMLTRT"))
      (libsource (lib "eagle-import") (part "SX1250"))
    )
    (comp (ref "U203")
      (value "B4377")
      (footprint "eagle-import:B4377")
      (fields (field (name "MPN") "B39871B4377P810"))
      (libsource (lib "eagle-import") (part "B4377"))
    )
    (comp (ref "U204")
      (value "B4377")
      (footprint "eagle-import:B4377")
      (fields (field (name "MPN") "B39871B4377P810"))
      (libsource (lib "eagle-import") (part "B4377"))
    )
    (comp (ref "U205")
      (value "SKY66420-11")
      (footprint "eagle-import:QFN50P300X300X80-17T170")
      (fields (field (name "MPN") "SKY66420-11"))
      (libsource (lib "eagle-import") (part "SKY66420-11"))
    )
    (comp (ref "U206")
      (value "B4377")
      (footprint "eagle-import:B4377")
      (fields (field (name "MPN") "B39871B4377P810"))
      (libsource (lib "eagle-import") (part "B4377"))
    )
    (comp (ref "U207")
      (value "PE4259")
      (footprint "eagle-import:SC70-6")
      (fields (field (name "MPN") "PE4259-63"))
      (libsource (lib "eagle-import") (part "PE4259"))
    )
    (comp (ref "X201")
      (value "32MHz <2.5ppm")
      (footprint "eagle-import:OSCCC250X200X90N")
      (fields
        (field (name "MPN") "ECS-TXO-25CSMV-320-AM-TR")
        (field (name "MPN-ALT") "ASTX-13-D-32,000MHZ-I05-T")
        (field (name "MPN-ALT2") "ATX-12-F-32,000MHZ-F05-T")
        (field (name "MPN-ALT3") "ECS-TXO-2520-33-320-AN")
      )
      (libsource (lib "eagle-import") (part "TCXO-DUAL-2016-2520"))
    )
    (comp (ref "BTN1")
      (value "TESPOINT-SMD1.5MM")
      (footprint "eagle-import:TESTPOINT-1.5MM")
      (libsource (lib "eagle-import") (part "TESPOINT-SMD1.5MM"))
    )
    (comp (ref "C301")
      (value "10uF")
      (footprint "eagle-import:C0603")
      (fields (field (name "MPN") "CL10A106KP8NNNC"))
      (libsource (lib "eagle-import") (part "CAPACITOR-NP-0603"))
    )
    (comp (ref "C302")
      (value "10uF")
      (footprint "eagle-import:C0603")
      (fields (field (name "MPN") "CL10A106KP8NNNC"))
      (libsource (lib "eagle-import") (part "CAPACITOR-NP-0603"))
    )
    (comp (ref "C303")
      (value "100nF")
      (footprint "eagle-import:C0402")
      (fields (field (name "MPN") "CC0402KRX7R7BB104"))
      (libsource (lib "eagle-import") (part "CAPACITOR-NP-0402"))
    )
    (comp (ref "ESP-!BOOT!")
      (value "TESPOINT-SMD1.5MM")
      (footprint "eagle-import:TESTPOINT-1.5MM")
      (libsource (lib "eagle-import") (part "TESPOINT-SMD1.5MM"))
    )
    (comp (ref "ESP-!RST!")
      (value "TESPOINT-SMD1.5MM")
      (footprint "eagle-import:TESTPOINT-1.5MM")
      (libsource (lib "eagle-import") (part "TESPOINT-SMD1.5MM"))
    )
    (comp (ref "ESP-RXI")
      (value "TESPOINT-SMD1.5MM")
      (footprint "eagle-import:TESTPOINT-1.5MM")
      (libsource (lib "eagle-import") (part "TESPOINT-SMD1.5MM"))
    )
    (comp (ref "ESP-TXO")
      (value "TESPOINT-SMD1.5MM")
      (footprint "eagle-import:TESTPOINT-1.5MM")
      (libsource (lib "eagle-import") (part "TESPOINT-SMD1.5MM"))
    )
    (comp (ref "ESP-VCC")
      (value "TESPOINT-SMD1.5MM")
      (footprint "eagle-import:TESTPOINT-1.5MM")
      (libsource (lib "eagle-import") (part "TESPOINT-SMD1.5MM"))
    )
    (comp (ref "FB301")
      (value ">1A 60R@100MHz DCR<0.1R")
      (footprint "eagle-import:FB0402")
      (fields (field (name "MPN") "BLM15PD600SN1D"))
      (libsource (lib "eagle-import") (part "FERRITE-0402"))
    )
    (comp (ref "GND")
      (value "TESPOINT-SMD1.5MM")
      (footprint "eagle-import:TESTPOINT-1.5MM")
      (libsource (lib "eagle-import") (part "TESPOINT-SMD1.5MM"))
    )
    (comp (ref "GND1")
      (value "TESPOINT-SMD1.5MM")
      (footprint "eagle-import:TESTPOINT-1.5MM")
      (libsource (lib "eagle-import") (part "TESPOINT-SMD1.5MM"))
    )
    (comp (ref "GND2")
      (value "TESPOINT-SMD1.5MM")
      (footprint "eagle-import:TESTPOINT-1.5MM")
      (libsource (lib "eagle-import") (part "TESPOINT-SMD1.5MM"))
    )
    (comp (ref "J301")
      (value "DNP")
      (footprint "eagle-import:533980567-PICOBLADE-5P-SMT-VER")
      (fields (field (name "MPN") "C37886 (MX 1.25T-5P)"))
      (libsource (lib "eagle-import") (part "533980567"))
    )
    (comp (ref "J302")
      (value "TC2030-ESP-NL")
      (footprint "eagle-import:TC2030-MCP-NL")
      (libsource (lib "eagle-import") (part "TC2030-ESP-NL"))
    )
    (comp (ref "LED301")
      (value "GREEN")
      (footprint "eagle-import:LED0603")
      (fields (field (name "MPN") "ORH-G36G"))
      (libsource (lib "eagle-import") (part "LED-0603"))
    )
    (comp (ref "LED302")
      (value "RED")
      (footprint "eagle-import:LED0603")
      (fields (field (name "MPN") "ORH-R36A"))
      (libsource (lib "eagle-import") (part "LED-0603"))
    )
    (comp (ref "R301")
      (value "10K")
      (footprint "eagle-import:R0402")
      (fields (field (name "MPN") "RC0402JR-0710KL"))
      (libsource (lib "eagle-import") (part "RESISTOR-0402"))
    )
    (comp (ref "R302")
      (value "1K")
      (footprint "eagle-import:R0402")
      (fields (field (name "MPN") "0402WGF1001TCE"))
      (libsource (lib "eagle-import") (part "RESISTOR-0402"))
    )
    (comp (ref "R303")
      (value "1K")
      (footprint "eagle-import:R0402")
      (fields (field (name "MPN") "0402WGF1001TCE"))
      (libsource (lib "eagle-import") (part "RESISTOR-0402"))
    )
    (comp (ref "R304")
      (value "20K")
      (footprint "eagle-import:R0402")
      (fields (field (name "MPN") "0402WGF2002TCE"))
      (libsource (lib "eagle-import") (part "RESISTOR-0402"))
    )
    (comp (ref "R305")
      (value "100K")
      (footprint "eagle-import:R0402")
      (fields (field (name "MPN") "0402WGF1003TCE"))
      (libsource (lib "eagle-import") (part "RESISTOR-0402"))
    )
    (comp (ref "S301")
      (value "K2-1102AQ-K4CW-01")
      (footprint "eagle-import:6MM-TH-RA")
      (libsource (lib "eagle-import") (part "TACTILE-SWITCH-GND"))
    )
    (comp (ref "U301")
      (value "ESP32-WROOM-32E(M113EH3200PH3Q0)")
      (footprint "eagle-import:ESP32-WROOM-32D")
      (fields (field (name "MPN") "ESP32-WROOM-32E(M113EH3200PH3Q0)"))
      (libsource (lib "eagle-import") (part "ESP32-WROOM-32D"))
    )
    (comp (ref "!PHY-RST!")
      (value "TESPOINT-SMD1.5MM")
      (footprint "eagle-import:TESTPOINT-1.5MM")
      (libsource (lib "eagle-import") (part "TESPOINT-SMD1.5MM"))
    )
    (comp (ref "C401")
      (value "100nF")
      (footprint "eagle-import:C0402")
      (fields (field (name "MPN") "CC0402KRX7R7BB104"))
      (libsource (lib "eagle-import") (part "CAPACITOR-NP-0402"))
    )
    (comp (ref "C402")
      (value "100nF")
      (footprint "eagle-import:C0402")
      (fields (field (name "MPN") "CC0402KRX7R7BB104"))
      (libsource (lib "eagle-import") (part "CAPACITOR-NP-0402"))
    )
    (comp (ref "C403")
      (value "10uF")
      (footprint "eagle-import:C0603")
      (fields (field (name "MPN") "CL10A106KP8NNNC"))
      (libsource (lib "eagle-import") (part "CAPACITOR-NP-0603"))
    )
    (comp (ref "C404")
      (value "10pF")
      (footprint "eagle-import:C0402")
      (fields (field (name "MPN") "CC0402JRNPO9BN100"))
      (libsource (lib "eagle-import") (part "CAPACITOR-NP-0402"))
    )
    (comp (ref "C405")
      (value "10pF")
      (footprint "eagle-import:C0402")
      (fields (field (name "MPN") "CC0402JRNPO9BN100"))
      (libsource (lib "eagle-import") (part "CAPACITOR-NP-0402"))
    )
    (comp (ref "C406")
      (value "100nF")
      (footprint "eagle-import:C0402")
      (fields (field (name "MPN") "CC0402KRX7R7BB104"))
      (libsource (lib "eagle-import") (part "CAPACITOR-NP-0402"))
    )
    (comp (ref "C407")
      (value "10uF")
      (footprint "eagle-import:C0603")
      (fields (field (name "MPN") "CL10A106KP8NNNC"))
      (libsource (lib "eagle-import") (part "CAPACITOR-NP-0603"))
    )
    (comp (ref "C408")
      (value "100nF")
      (footprint "eagle-import:C0402")
      (fields (field (name "MPN") "CC0402KRX7R7BB104"))
      (libsource (lib "eagle-import") (part "CAPACITOR-NP-0402"))
    )
    (comp (ref "C409")
      (value "10uF")
      (footprint "eagle-import:C0603")
      (fields (field (name "MPN") "CL10A106KP8NNNC"))
      (libsource (lib "eagle-import") (part "CAPACITOR-NP-0603"))
    )
    (comp (ref "C410")
      (value "10pF")
      (footprint "eagle-import:C0402")
      (fields (field (name "MPN") "CC0402JRNPO9BN100"))
      (libsource (lib "eagle-import") (part "CAPACITOR-NP-0402"))
    )
    (comp (ref "C411")
      (value "10pF")
      (footprint "eagle-import:C0402")
      (fields (field (name "MPN") "CC0402JRNPO9BN100"))
      (libsource (lib "eagle-import") (part "CAPACITOR-NP-0402"))
    )
    (comp (ref "C412")
      (value "10pF")
      (footprint "eagle-import:C0402")
      (fields (field (name "MPN") "CC0402JRNPO9BN100"))
      (libsource (lib "eagle-import") (part "CAPACITOR-NP-0402"))
    )
    (comp (ref "C413")
      (value "10pF")
      (footprint "eagle-import:C0402")
      (fields (field (name "MPN") "CC0402JRNPO9BN100"))
      (libsource (lib "eagle-import") (part "CAPACITOR-NP-0402"))
    )
    (comp (ref "C414")
      (value "100nF")
      (footprint "eagle-import:C0402")
      (fields (field (name "MPN") "CC0402KRX7R7BB104"))
      (libsource (lib "eagle-import") (part "CAPACITOR-NP-0402"))
    )
    (comp (ref "C415")
      (value "100nF")
      (footprint "eagle-import:C0402")
      (fields (field (name "MPN") "CC0402KRX7R7BB104"))
      (libsource (lib "eagle-import") (part "CAPACITOR-NP-0402"))
    )
    (comp (ref "C416")
      (value "1nF 1kV")
      (footprint "eagle-import:C1206-H0.8")
      (fields (field (name "MPN") "FV31X102K102ECG"))
      (libsource (lib "eagle-import") (part "CAPACITOR-NP-1206-H0.8"))
    )
    (comp (ref "FB401")
      (value ">1A 60R@100MHz DCR<0.1R")
      (footprint "eagle-import:FB0402")
      (fields (field (name "MPN") "BLM15PD600SN1D"))
      (libsource (lib "eagle-import") (part "FERRITE-0402"))
    )
    (comp (ref "J401")
      (value "HR913550A")
      (footprint "eagle-import:RJ45_8P_TH_2LED")
      (fields (field (name "MPN-ALT") "7499010441"))
      (libsource (lib "eagle-import") (part "RJ45"))
    )
    (comp (ref "PHY-TEST")
      (value "TESPOINT-SMD1.5MM")
      (footprint "eagle-import:TESTPOINT-1.5MM")
      (libsource (lib "eagle-import") (part "TESPOINT-SMD1.5MM"))
    )
    (comp (ref "R401")
      (value "10K")
      (footprint "eagle-import:R0402")
      (fields (field (name "MPN") "RC0402JR-0710KL"))
      (libsource (lib "eagle-import") (part "RESISTOR-0402"))
    )
    (comp (ref "R402")
      (value "10R")
      (footprint "eagle-import:R0402")
      (fields (field (name "MPN") "RC0402JR-0710RL"))
      (libsource (lib "eagle-import") (part "RESISTOR-0402"))
    )
    (comp (ref "R403")
      (value "5.1K")
      (footprint "eagle-import:R0402")
      (fields (field (name "MPN") "0402WGF5101TCE"))
      (libsource (lib "eagle-import") (part "RESISTOR-0402"))
    )
    (comp (ref "R404")
      (value "10R")
      (footprint "eagle-import:R0402")
      (fields (field (name "MPN") "RC0402JR-0710RL"))
      (libsource (lib "eagle-import") (part "RESISTOR-0402"))
    )
    (comp (ref "R405")
      (value "10R")
      (footprint "eagle-import:R0402")
      (fields (field (name "MPN") "RC0402JR-0710RL"))
      (libsource (lib "eagle-import") (part "RESISTOR-0402"))
    )
    (comp (ref "R406")
      (value "0R")
      (footprint "eagle-import:R0402")
      (fields (field (name "MPN") "RC0402JR-070RL"))
      (libsource (lib "eagle-import") (part "RESISTOR-0402"))
    )
    (comp (ref "R407")
      (value "5.1K")
      (footprint "eagle-import:R0402")
      (fields (field (name "MPN") "0402WGF5101TCE"))
      (libsource (lib "eagle-import") (part "RESISTOR-0402"))
    )
    (comp (ref "R408")
      (value "10R")
      (footprint "eagle-import:R0402")
      (fields (field (name "MPN") "RC0402JR-0710RL"))
      (libsource (lib "eagle-import") (part "RESISTOR-0402"))
    )
    (comp (ref "R409")
      (value "10R")
      (footprint "eagle-import:R0402")
      (fields (field (name "MPN") "RC0402JR-0710RL"))
      (libsource (lib "eagle-import") (part "RESISTOR-0402"))
    )
    (comp (ref "R410")
      (value "10R")
      (footprint "eagle-import:R0402")
      (fields (field (name "MPN") "RC0402JR-0710RL"))
      (libsource (lib "eagle-import") (part "RESISTOR-0402"))
    )
    (comp (ref "R411")
      (value "5.1K")
      (footprint "eagle-import:R0402")
      (fields (field (name "MPN") "0402WGF5101TCE"))
      (libsource (lib "eagle-import") (part "RESISTOR-0402"))
    )
    (comp (ref "R412")
      (value "5.1K")
      (footprint "eagle-import:R0402")
      (fields (field (name "MPN") "0402WGF5101TCE"))
      (libsource (lib "eagle-import") (part "RESISTOR-0402"))
    )
    (comp (ref "R413")
      (value "10K")
      (footprint "eagle-import:R0402")
      (fields (field (name "MPN") "RC0402JR-0710KL"))
      (libsource (lib "eagle-import") (part "RESISTOR-0402"))
    )
    (comp (ref "R414")
      (value "6.19K 1%")
      (footprint "eagle-import:R0402")
      (fields (field (name "MPN") "0402WGF6191TCE"))
      (libsource (lib "eagle-import") (part "RESISTOR-0402"))
    )
    (comp (ref "R415")
      (value "330R")
      (footprint "eagle-import:R0402")
      (fields (field (name "MPN") "0402WGF3300TCE"))
      (libsource (lib "eagle-import") (part "RESISTOR-0402"))
    )
    (comp (ref "R416")
      (value "330R")
      (footprint "eagle-import:R0402")
      (fields (field (name "MPN") "0402WGF3300TCE"))
      (libsource (lib "eagle-import") (part "RESISTOR-0402"))
    )
    (comp (ref "R417")
      (value "5.1K")
      (footprint "eagle-import:R0402")
      (fields (field (name "MPN") "0402WGF5101TCE"))
      (libsource (lib "eagle-import") (part "RESISTOR-0402"))
    )
    (comp (ref "R418")
      (value "5.1K")
      (footprint "eagle-import:R0402")
      (fields (field (name "MPN") "0402WGF5101TCE"))
      (libsource (lib "eagle-import") (part "RESISTOR-0402"))
    )
    (comp (ref "R419")
      (value "DNP")
      (footprint "eagle-import:R1206")
      (fields (field (name "MPN") "WR04X0000FTL"))
      (libsource (lib "eagle-import") (part "RESISTOR-1206"))
    )
    (comp (ref "U401")
      (value "IP101G")
      (footprint "eagle-import:QFN40P400X400X90-33T275N")
      (fields (field (name "MPN") "IP101GR"))
      (libsource (lib "eagle-import") (part "IP101G"))
    )
    (comp (ref "X401")
      (value "25MHz")
      (footprint "eagle-import:OSCCC350X250X80")
      (fields (field (name "MPN") "X322525MOB4SI"))
      (libsource (lib "eagle-import") (part "CRYSTAL-GND-3.5X2.5-4P"))
    )
    (comp (ref "3V3")
      (value "TESPOINT-SMD1.5MM")
      (footprint "eagle-import:TESTPOINT-1.5MM")
      (libsource (lib "eagle-import") (part "TESPOINT-SMD1.5MM"))
    )
    (comp (ref "3V3-FEM")
      (value "TESPOINT-SMD1.5MM")
      (footprint "eagle-import:TESTPOINT-1.5MM")
      (libsource (lib "eagle-import") (part "TESPOINT-SMD1.5MM"))
    )
    (comp (ref "3V3-RF")
      (value "TESPOINT-SMD1.5MM")
      (footprint "eagle-import:TESTPOINT-1.5MM")
      (libsource (lib "eagle-import") (part "TESPOINT-SMD1.5MM"))
    )
    (comp (ref "C501")
      (value "10uF")
      (footprint "eagle-import:C0603")
      (fields (field (name "MPN") "CL10A106KP8NNNC"))
      (libsource (lib "eagle-import") (part "CAPACITOR-NP-0603"))
    )
    (comp (ref "C502")
      (value "10uF")
      (footprint "eagle-import:C0603")
      (fields (field (name "MPN") "CL10A106KP8NNNC"))
      (libsource (lib "eagle-import") (part "CAPACITOR-NP-0603"))
    )
    (comp (ref "C503")
      (value "10uF")
      (footprint "eagle-import:C0603")
      (fields (field (name "MPN") "CL10A106KP8NNNC"))
      (libsource (lib "eagle-import") (part "CAPACITOR-NP-0603"))
    )
    (comp (ref "C504")
      (value "100nF")
      (footprint "eagle-import:C0402")
      (fields (field (name "MPN") "CC0402KRX7R7BB104"))
      (libsource (lib "eagle-import") (part "CAPACITOR-NP-0402"))
    )
    (comp (ref "C505")
      (value "10uF")
      (footprint "eagle-import:C0603")
      (fields (field (name "MPN") "CL10A106KP8NNNC"))
      (libsource (lib "eagle-import") (part "CAPACITOR-NP-0603"))
    )
    (comp (ref "C506")
      (value "10uF")
      (footprint "eagle-import:C0603")
      (fields (field (name "MPN") "CL10A106KP8NNNC"))
      (libsource (lib "eagle-import") (part "CAPACITOR-NP-0603"))
    )
    (comp (ref "C507")
      (value "10uF")
      (footprint "eagle-import:C0603")
      (fields (field (name "MPN") "CL10A106KP8NNNC"))
      (libsource (lib "eagle-import") (part "CAPACITOR-NP-0603"))
    )
    (comp (ref "C508")
      (value "10uF")
      (footprint "eagle-import:C0603")
      (fields (field (name "MPN") "CL10A106KP8NNNC"))
      (libsource (lib "eagle-import") (part "CAPACITOR-NP-0603"))
    )
    (comp (ref "C509")
      (value "10uF")
      (footprint "eagle-import:C0603")
      (fields (field (name "MPN") "CL10A106KP8NNNC"))
      (libsource (lib "eagle-import") (part "CAPACITOR-NP-0603"))
    )
    (comp (ref "C510")
      (value "100nF")
      (footprint "eagle-import:C0402")
      (fields (field (name "MPN") "CC0402KRX7R7BB104"))
      (libsource (lib "eagle-import") (part "CAPACITOR-NP-0402"))
    )
    (comp (ref "C511")
      (value "100nF")
      (footprint "eagle-import:C0402")
      (fields (field (name "MPN") "CC0402KRX7R7BB104"))
      (libsource (lib "eagle-import") (part "CAPACITOR-NP-0402"))
    )
    (comp (ref "C512")
      (value "100nF")
      (footprint "eagle-import:C0402")
      (fields (field (name "MPN") "CC0402KRX7R7BB104"))
      (libsource (lib "eagle-import") (part "CAPACITOR-NP-0402"))
    )
    (comp (ref "C513")
      (value "100nF")
      (footprint "eagle-import:C0402")
      (fields (field (name "MPN") "CC0402KRX7R7BB104"))
      (libsource (lib "eagle-import") (part "CAPACITOR-NP-0402"))
    )
    (comp (ref "F501")
      (value "1.5/3A 8V")
      (footprint "eagle-import:1210")
      (fields (field (name "MPN") "1206L150THWR"))
      (libsource (lib "eagle-import") (part "FUSE1210"))
    )
    (comp (ref "FB501")
      (value ">1A 60R@100MHz DCR<0.1R")
      (footprint "eagle-import:FB0402")
      (fields (field (name "MPN") "BLM15PD600SN1D"))
      (libsource (lib "eagle-import") (part "FERRITE-0402"))
    )
    (comp (ref "FB502")
      (value ">1A 60R@100MHz DCR<0.1R")
      (footprint "eagle-import:FB0402")
      (fields (field (name "MPN") "BLM15PD600SN1D"))
      (libsource (lib "eagle-import") (part "FERRITE-0402"))
    )
    (comp (ref "FB503")
      (value ">1A 60R@100MHz DCR<0.1R")
      (footprint "eagle-import:FB0402")
      (fields (field (name "MPN") "BLM15PD600SN1D"))
      (libsource (lib "eagle-import") (part "FERRITE-0402"))
    )
    (comp (ref "FB504")
      (value ">1A 60R@100MHz DCR<0.1R")
      (footprint "eagle-import:FB0402")
      (fields (field (name "MPN") "BLM15PD600SN1D"))
      (libsource (lib "eagle-import") (part "FERRITE-0402"))
    )
    (comp (ref "J501")
      (value "U254-051N-4BH806")
      (footprint "eagle-import:USB_MICRO_3")
      (libsource (lib "eagle-import") (part "MICRO_USB"))
    )
    (comp (ref "L501")
      (value "2.2uH")
      (footprint "eagle-import:1008")
      (fields (field (name "MPN") "252012CDMCDDS-2R2MC"))
      (libsource (lib "eagle-import") (part "INDUCTOR-1008"))
    )
    (comp (ref "L502")
      (value "2.2uH")
      (footprint "eagle-import:1008")
      (fields (field (name "MPN") "252012CDMCDDS-2R2MC"))
      (libsource (lib "eagle-import") (part "INDUCTOR-1008"))
    )
    (comp (ref "R501")
      (value "1K")
      (footprint "eagle-import:R0402")
      (fields (field (name "MPN") "0402WGF1001TCE"))
      (libsource (lib "eagle-import") (part "RESISTOR-0402"))
    )
    (comp (ref "R502")
      (value "120K 1%")
      (footprint "eagle-import:R0402")
      (fields (field (name "MPN") "0402WGF1203TCE"))
      (libsource (lib "eagle-import") (part "RESISTOR-0402"))
    )
    (comp (ref "R503")
      (value "150K 1%")
      (footprint "eagle-import:R0402")
      (fields (field (name "MPN") "WR04X1503FTL"))
      (libsource (lib "eagle-import") (part "RESISTOR-0402"))
    )
    (comp (ref "R504")
      (value "120K 1%")
      (footprint "eagle-import:R0402")
      (fields (field (name "MPN") "0402WGF1203TCE"))
      (libsource (lib "eagle-import") (part "RESISTOR-0402"))
    )
    (comp (ref "R505")
      (value "680K 1%")
      (footprint "eagle-import:R0402")
      (fields (field (name "MPN") "WR04X6803FTL"))
      (libsource (lib "eagle-import") (part "RESISTOR-0402"))
    )
    (comp (ref "REG-EN")
      (value "TESPOINT-SMD1.5MM")
      (footprint "eagle-import:TESTPOINT-1.5MM")
      (libsource (lib "eagle-import") (part "TESPOINT-SMD1.5MM"))
    )
    (comp (ref "SJ501")
      (value "JUMPER2-NC-0603")
      (footprint "eagle-import:JUMPER2-0603_NC")
      (libsource (lib "eagle-import") (part "JUMPER2-NC-0603"))
    )
    (comp (ref "SJ502")
      (value "JUMPER2-NC-0603")
      (footprint "eagle-import:JUMPER2-0603_NC")
      (libsource (lib "eagle-import") (part "JUMPER2-NC-0603"))
    )
    (comp (ref "SX-VCC-CORE")
      (value "TESPOINT-SMD1.5MM")
      (footprint "eagle-import:TESTPOINT-1.5MM")
      (libsource (lib "eagle-import") (part "TESPOINT-SMD1.5MM"))
    )
    (comp (ref "U501")
      (value "BL8028CB5TR")
      (footprint "eagle-import:SOT95P280X120-5")
      (fields (field (name "MPN") "BL8028CB5TR"))
      (libsource (lib "eagle-import") (part "REG-DC/DC"))
    )
    (comp (ref "U502")
      (value "BL8028CB5TR")
      (footprint "eagle-import:SOT95P280X120-5")
      (fields (field (name "MPN") "BL8028CB5TR"))
      (libsource (lib "eagle-import") (part "REG-DC/DC"))
    )
    (comp (ref "U503")
      (value "NCP176BMX330TCG")
      (footprint "eagle-import:SON40P120X120X80-7T40X108N")
      (fields (field (name "MPN") "NCP176BMX330TCG"))
      (libsource (lib "eagle-import") (part "REG_LDO5P-DFN6"))
    )
    (comp (ref "USB-DN")
      (value "TESPOINT-SMD1.5MM")
      (footprint "eagle-import:TESTPOINT-1.5MM")
      (libsource (lib "eagle-import") (part "TESPOINT-SMD1.5MM"))
    )
    (comp (ref "USB-DP")
      (value "TESPOINT-SMD1.5MM")
      (footprint "eagle-import:TESTPOINT-1.5MM")
      (libsource (lib "eagle-import") (part "TESPOINT-SMD1.5MM"))
    )
    (comp (ref "VCC")
      (value "TESPOINT-SMD1.5MM")
      (footprint "eagle-import:TESTPOINT-1.5MM")
      (libsource (lib "eagle-import") (part "TESPOINT-SMD1.5MM"))
    )
  )
  (nets
    (net (code "1") (name "3V3") (class "Default")
      (node (ref "3V3") (pin "1") (pinfunction "P$1_1") (pintype "bidirectional"))
      (node (ref "C103") (pin "2") (pinfunction "2_2") (pintype "bidirectional"))
      (node (ref "C104") (pin "2") (pinfunction "2_2") (pintype "bidirectional"))
      (node (ref "C105") (pin "2") (pinfunction "2_2") (pintype "bidirectional"))
      (node (ref "C106") (pin "2") (pinfunction "2_2") (pintype "bidirectional"))
      (node (ref "C408") (pin "2") (pinfunction "2_2") (pintype "bidirectional"))
      (node (ref "C409") (pin "2") (pinfunction "2_2") (pintype "bidirectional"))
      (node (ref "C513") (pin "2") (pinfunction "2_2") (pintype "bidirectional"))
      (node (ref "C601") (pin "2") (pinfunction "2_2") (pintype "bidirectional"))
      (node (ref "C602") (pin "2") (pinfunction "2_2") (pintype "bidirectional"))
      (node (ref "FB203") (pin "1") (pinfunction "1_1") (pintype "bidirectional"))
      (node (ref "FB301") (pin "2") (pinfunction "2_2") (pintype "bidirectional"))
      (node (ref "FB401") (pin "2") (pinfunction "2_2") (pintype "bidirectional"))
      (node (ref "FB503") (pin "2") (pinfunction "2_2") (pintype "bidirectional"))
      (node (ref "J401") (pin "11") (pinfunction "A_11") (pintype "passive"))
      (node (ref "R104") (pin "1") (pinfunction "1_1") (pintype "bidirectional"))
      (node (ref "R105") (pin "1") (pinfunction "1_1") (pintype "bidirectional"))
      (node (ref "R203") (pin "1") (pinfunction "1_1") (pintype "bidirectional"))
      (node (ref "R304") (pin "1") (pinfunction "1_1") (pintype "bidirectional"))
      (node (ref "R305") (pin "2") (pinfunction "2_2") (pintype "bidirectional"))
      (node (ref "R407") (pin "2") (pinfunction "2_2") (pintype "bidirectional"))
      (node (ref "R411") (pin "2") (pinfunction "2_2") (pintype "bidirectional"))
      (node (ref "R412") (pin "2") (pinfunction "2_2") (pintype "bidirectional"))
      (node (ref "R413") (pin "2") (pinfunction "2_2") (pintype "bidirectional"))
      (node (ref "R417") (pin "1") (pinfunction "1_1") (pintype "bidirectional"))
      (node (ref "U101") (pin "14") (pinfunction "VCC_IO_14") (pintype "bidirectional"))
      (node (ref "U101") (pin "30") (pinfunction "VCC_IO_30") (pintype "bidirectional"))
      (node (ref "U101") (pin "47") (pinfunction "VCC_IO_47") (pintype "bidirectional"))
      (node (ref "U101") (pin "61") (pinfunction "VCC_IO_61") (pintype "bidirectional"))
      (node (ref "U401") (pin "13") (pinfunction "VDDIO_13") (pintype "bidirectional"))
      (node (ref "U601") (pin "16") (pinfunction "VCC_16") (pintype "bidirectional"))
      (node (ref "U601") (pin "4") (pinfunction "V3_4") (pintype "bidirectional"))
    )
    (net (code "2") (name "3V3_FEM") (class "Default")
      (node (ref "3V3-FEM") (pin "1") (pinfunction "P$1_1") (pintype "bidirectional"))
      (node (ref "C225") (pin "2") (pinfunction "2_2") (pintype "bidirectional"))
      (node (ref "C226") (pin "1") (pinfunction "1_1") (pintype "bidirectional"))
      (node (ref "C230") (pin "2") (pinfunction "2_2") (pintype "bidirectional"))
      (node (ref "C231") (pin "1") (pinfunction "1_1") (pintype "bidirectional"))
      (node (ref "C232") (pin "1") (pinfunction "1_1") (pintype "bidirectional"))
      (node (ref "C251") (pin "2") (pinfunction "2_2") (pintype "bidirectional"))
      (node (ref "C510") (pin "2") (pinfunction "2_2") (pintype "bidirectional"))
      (node (ref "FB501") (pin "2") (pinfunction "2_2") (pintype "bidirectional"))
      (node (ref "L208") (pin "2") (pinfunction "2_2") (pintype "bidirectional"))
      (node (ref "L209") (pin "2") (pinfunction "2_2") (pintype "bidirectional"))
      (node (ref "R213") (pin "2") (pinfunction "2_2") (pintype "bidirectional"))
      (node (ref "U205") (pin "15") (pinfunction "VCC0_15") (pintype "bidirectional"))
      (node (ref "U207") (pin "6") (pinfunction "VDD_6") (pintype "bidirectional"))
    )
    (net (code "3") (name "3V3_RF") (class "Default")
      (node (ref "3V3-RF") (pin "1") (pinfunction "P$1_1") (pintype "bidirectional"))
      (node (ref "C201") (pin "2") (pinfunction "2_2") (pintype "bidirectional"))
      (node (ref "C202") (pin "2") (pinfunction "2_2") (pintype "bidirectional"))
      (node (ref "C206") (pin "2") (pinfunction "2_2") (pintype "bidirectional"))
      (node (ref "C208") (pin "2") (pinfunction "2_2") (pintype "bidirectional"))
      (node (ref "C512") (pin "2") (pinfunction "2_2") (pintype "bidirectional"))
      (node (ref "FB201") (pin "1") (pinfunction "1_1") (pintype "bidirectional"))
      (node (ref "FB202") (pin "1") (pinfunction "1_1") (pintype "bidirectional"))
      (node (ref "FB504") (pin "2") (pinfunction "2_2") (pintype "bidirectional"))
      (node (ref "U201") (pin "10") (pinfunction "VBAT_DIO_10") (pintype "bidirectional"))
      (node (ref "U201") (pin "2") (pinfunction "VDD_IN_2") (pintype "bidirectional"))
      (node (ref "U201") (pin "9") (pinfunction "VBAT_RF_9") (pintype "bidirectional"))
      (node (ref "U202") (pin "10") (pinfunction "VBAT_DIO_10") (pintype "bidirectional"))
      (node (ref "U202") (pin "2") (pinfunction "VDD_IN_2") (pintype "bidirectional"))
      (node (ref "U202") (pin "9") (pinfunction "VBAT_RF_9") (pintype "bidirectional"))
    )
    (net (code "4") (name "ANT_SEL") (class "Default")
      (node (ref "ANT-SEL") (pin "1") (pinfunction "P$1_1") (pintype "bidirectional"))
      (node (ref "R213") (pin "1") (pinfunction "1_1") (pintype "bidirectional"))
      (node (ref "R214") (pin "1") (pinfunction "1_1") (pintype "bidirectional"))
      (node (ref "U101") (pin "54") (pinfunction "GPIO_7_54") (pintype "bidirectional"))
    )
    (net (code "5") (name "BTN1") (class "Default")
      (node (ref "BTN1") (pin "1") (pinfunction "P$1_1") (pintype "bidirectional"))
      (node (ref "C303") (pin "2") (pinfunction "2_2") (pintype "bidirectional"))
      (node (ref "R305") (pin "1") (pinfunction "1_1") (pintype "bidirectional"))
      (node (ref "S301") (pin "2") (pinfunction "2_2") (pintype "passive"))
      (node (ref "U301") (pin "7") (pinfunction "IO35_7") (pintype "bidirectional"))
    )
    (net (code "6") (name "DTR") (class "Default")
      (node (ref "Q601") (pin "2") (pinfunction "E_2") (pintype "passive"))
      (node (ref "R602") (pin "2") (pinfunction "2_2") (pintype "bidirectional"))
      (node (ref "U601") (pin "13") (pinfunction "DTR#_13") (pintype "bidirectional"))
    )
    (net (code "7") (name "EMAC_MDC") (class "Default")
      (node (ref "U301") (pin "9") (pinfunction "IO33_9") (pintype "bidirectional"))
      (node (ref "U401") (pin "22") (pinfunction "MDC_22") (pintype "bidirectional"))
    )
    (net (code "8") (name "EMAC_MDIO") (class "Default")
      (node (ref "R413") (pin "1") (pinfunction "1_1") (pintype "bidirectional"))
      (node (ref "U301") (pin "8") (pinfunction "IO32_8") (pintype "bidirectional"))
      (node (ref "U401") (pin "23") (pinfunction "MDIO_23") (pintype "bidirectional"))
    )
    (net (code "9") (name "EMAC_RXD0") (class "Default")
      (node (ref "R408") (pin "1") (pinfunction "1_1") (pintype "bidirectional"))
      (node (ref "U301") (pin "10") (pinfunction "IO25_10") (pintype "bidirectional"))
    )
    (net (code "10") (name "EMAC_RXD1") (class "Default")
      (node (ref "R409") (pin "1") (pinfunction "1_1") (pintype "bidirectional"))
      (node (ref "U301") (pin "11") (pinfunction "IO26_11") (pintype "bidirectional"))
    )
    (net (code "11") (name "EMAC_RX_DV") (class "Default")
      (node (ref "R410") (pin "1") (pinfunction "1_1") (pintype "bidirectional"))
      (node (ref "U301") (pin "12") (pinfunction "IO27_12") (pintype "bidirectional"))
    )
    (net (code "12") (name "EMAC_TXD0") (class "Default")
      (node (ref "R404") (pin "1") (pinfunction "1_1") (pintype "bidirectional"))
      (node (ref "U301") (pin "31") (pinfunction "IO19_31") (pintype "bidirectional"))
    )
    (net (code "13") (name "EMAC_TXD1") (class "Default")
      (node (ref "R405") (pin "1") (pinfunction "1_1") (pintype "bidirectional"))
      (node (ref "U301") (pin "36") (pinfunction "IO22_36") (pintype "bidirectional"))
    )
    (net (code "14") (name "EMAC_TX_EN") (class "Default")
      (node (ref "U301") (pin "33") (pinfunction "IO21_33") (pintype "bidirectional"))
      (node (ref "U401") (pin "5") (pinfunction "TXEN_5") (pintype "bidirectional"))
    )
    (net (code "15") (name "ESP_RXI") (class "Default")
      (node (ref "ESP-RXI") (pin "1") (pinfunction "P$1_1") (pintype "bidirectional"))
      (node (ref "J302") (pin "4") (pinfunction "TARGET_RXI_4") (pintype "bidirectional"))
      (node (ref "U301") (pin "34") (pinfunction "RXD0_34") (pintype "bidirectional"))
      (node (ref "U601") (pin "2") (pinfunction "TX_2") (pintype "bidirectional"))
    )
    (net (code "16") (name "ESP_TXO") (class "Default")
      (node (ref "ESP-TXO") (pin "1") (pinfunction "P$1_1") (pintype "bidirectional"))
      (node (ref "J302") (pin "6") (pinfunction "TARGET_TXO_6") (pintype "bidirectional"))
      (node (ref "U301") (pin "35") (pinfunction "TXD0_35") (pintype "bidirectional"))
      (node (ref "U601") (pin "3") (pinfunction "RX_3") (pintype "bidirectional"))
    )
    (net (code "17") (name "EXP-EXT_INT") (class "Default")
      (node (ref "J301") (pin "1") (pinfunction "1_1") (pintype "bidirectional"))
      (node (ref "U301") (pin "37") (pinfunction "IO23_37") (pintype "bidirectional"))
    )
    (net (code "18") (name "EXP-SCL") (class "Default")
      (node (ref "J301") (pin "3") (pinfunction "3_3") (pintype "bidirectional"))
      (node (ref "U301") (pin "29") (pinfunction "IO5_29") (pintype "bidirectional"))
    )
    (net (code "19") (name "EXP-SDA") (class "Default")
      (node (ref "J301") (pin "2") (pinfunction "2_2") (pintype "bidirectional"))
      (node (ref "U301") (pin "30") (pinfunction "IO18_30") (pintype "bidirectional"))
    )
    (net (code "20") (name "FEM_CSD") (class "Default")
      (node (ref "C227") (pin "2") (pinfunction "2_2") (pintype "bidirectional"))
      (node (ref "R207") (pin "2") (pinfunction "2_2") (pintype "bidirectional"))
      (node (ref "U205") (pin "4") (pinfunction "CSD_4") (pintype "bidirectional"))
    )
    (net (code "21") (name "FEM_PA_ON") (class "Default")
      (node (ref "C229") (pin "2") (pinfunction "2_2") (pintype "bidirectional"))
      (node (ref "R209") (pin "2") (pinfunction "2_2") (pintype "bidirectional"))
      (node (ref "U205") (pin "5") (pinfunction "CPS_5") (pintype "bidirectional"))
    )
    (net (code "22") (name "FEM_RXTX_SW") (class "Default")
      (node (ref "C228") (pin "2") (pinfunction "2_2") (pintype "bidirectional"))
      (node (ref "R208") (pin "2") (pinfunction "2_2") (pintype "bidirectional"))
      (node (ref "U205") (pin "6") (pinfunction "CTX_6") (pintype "bidirectional"))
    )
    (net (code "23") (name "GND") (class "Default")
      (node (ref "C101") (pin "1") (pinfunction "1_1") (pintype "bidirectional"))
      (node (ref "C102") (pin "1") (pinfunction "1_1") (pintype "bidirectional"))
      (node (ref "C103") (pin "1") (pinfunction "1_1") (pintype "bidirectional"))
      (node (ref "C104") (pin "1") (pinfunction "1_1") (pintype "bidirectional"))
      (node (ref "C105") (pin "1") (pinfunction "1_1") (pintype "bidirectional"))
      (node (ref "C106") (pin "1") (pinfunction "1_1") (pintype "bidirectional"))
      (node (ref "C107") (pin "1") (pinfunction "1_1") (pintype "bidirectional"))
      (node (ref "C108") (pin "1") (pinfunction "1_1") (pintype "bidirectional"))
      (node (ref "C109") (pin "1") (pinfunction "1_1") (pintype "bidirectional"))
      (node (ref "C110") (pin "1") (pinfunction "1_1") (pintype "bidirectional"))
      (node (ref "C201") (pin "1") (pinfunction "1_1") (pintype "bidirectional"))
      (node (ref "C202") (pin "1") (pinfunction "1_1") (pintype "bidirectional"))
      (node (ref "C203") (pin "1") (pinfunction "1_1") (pintype "bidirectional"))
      (node (ref "C204") (pin "1") (pinfunction "1_1") (pintype "bidirectional"))
      (node (ref "C206") (pin "1") (pinfunction "1_1") (pintype "bidirectional"))
      (node (ref "C208") (pin "1") (pinfunction "1_1") (pintype "bidirectional"))
      (node (ref "C209") (pin "1") (pinfunction "1_1") (pintype "bidirectional"))
      (node (ref "C210") (pin "1") (pinfunction "1_1") (pintype "bidirectional"))
      (node (ref "C211") (pin "1") (pinfunction "1_1") (pintype "bidirectional"))
      (node (ref "C212") (pin "1") (pinfunction "1_1") (pintype "bidirectional"))
      (node (ref "C213") (pin "1") (pinfunction "1_1") (pintype "bidirectional"))
      (node (ref "C216") (pin "1") (pinfunction "1_1") (pintype "bidirectional"))
      (node (ref "C217") (pin "1") (pinfunction "1_1") (pintype "bidirectional"))
      (node (ref "C219") (pin "1") (pinfunction "1_1") (pintype "bidirectional"))
      (node (ref "C221") (pin "1") (pinfunction "1_1") (pintype "bidirectional"))
      (node (ref "C222") (pin "1") (pinfunction "1_1") (pintype "bidirectional"))
      (node (ref "C225") (pin "1") (pinfunction "1_1") (pintype "bidirectional"))
      (node (ref "C226") (pin "2") (pinfunction "2_2") (pintype "bidirectional"))
      (node (ref "C227") (pin "1") (pinfunction "1_1") (pintype "bidirectional"))
      (node (ref "C228") (pin "1") (pinfunction "1_1") (pintype "bidirectional"))
      (node (ref "C229") (pin "1") (pinfunction "1_1") (pintype "bidirectional"))
      (node (ref "C230") (pin "1") (pinfunction "1_1") (pintype "bidirectional"))
      (node (ref "C231") (pin "2") (pinfunction "2_2") (pintype "bidirectional"))
      (node (ref "C232") (pin "2") (pinfunction "2_2") (pintype "bidirectional"))
      (node (ref "C233") (pin "2") (pinfunction "2_2") (pintype "bidirectional"))
      (node (ref "C234") (pin "2") (pinfunction "2_2") (pintype "bidirectional"))
      (node (ref "C238") (pin "2") (pinfunction "2_2") (pintype "bidirectional"))
      (node (ref "C239") (pin "2") (pinfunction "2_2") (pintype "bidirectional"))
      (node (ref "C240") (pin "2") (pinfunction "2_2") (pintype "bidirectional"))
      (node (ref "C243") (pin "2") (pinfunction "2_2") (pintype "bidirectional"))
      (node (ref "C244") (pin "2") (pinfunction "2_2") (pintype "bidirectional"))
      (node (ref "C245") (pin "2") (pinfunction "2_2") (pintype "bidirectional"))
      (node (ref "C247") (pin "2") (pinfunction "2_2") (pintype "bidirectional"))
      (node (ref "C248") (pin "2") (pinfunction "2_2") (pintype "bidirectional"))
      (node (ref "C250") (pin "1") (pinfunction "1_1") (pintype "bidirectional"))
      (node (ref "C251") (pin "1") (pinfunction "1_1") (pintype "bidirectional"))
      (node (ref "C301") (pin "1") (pinfunction "1_1") (pintype "bidirectional"))
      (node (ref "C302") (pin "1") (pinfunction "1_1") (pintype "bidirectional"))
      (node (ref "C303") (pin "1") (pinfunction "1_1") (pintype "bidirectional"))
      (node (ref "C401") (pin "1") (pinfunction "1_1") (pintype "bidirectional"))
      (node (ref "C402") (pin "1") (pinfunction "1_1") (pintype "bidirectional"))
      (node (ref "C403") (pin "1") (pinfunction "1_1") (pintype "bidirectional"))
      (node (ref "C404") (pin "1") (pinfunction "1_1") (pintype "bidirectional"))
      (node (ref "C405") (pin "1") (pinfunction "1_1") (pintype "bidirectional"))
      (node (ref "C406") (pin "1") (pinfunction "1_1") (pintype "bidirectional"))
      (node (ref "C407") (pin "1") (pinfunction "1_1") (pintype "bidirectional"))
      (node (ref "C408") (pin "1") (pinfunction "1_1") (pintype "bidirectional"))
      (node (ref "C409") (pin "1") (pinfunction "1_1") (pintype "bidirectional"))
      (node (ref "C410") (pin "1") (pinfunction "1_1") (pintype "bidirectional"))
      (node (ref "C411") (pin "1") (pinfunction "1_1") (pintype "bidirectional"))
      (node (ref "C412") (pin "1") (pinfunction "1_1") (pintype "bidirectional"))
      (node (ref "C413") (pin "1") (pinfunction "1_1") (pintype "bidirectional"))
      (node (ref "C414") (pin "1") (pinfunction "1_1") (pintype "bidirectional"))
      (node (ref "C415") (pin "1") (pinfunction "1_1") (pintype "bidirectional"))
      (node (ref "C416") (pin "1") (pinfunction "1_1") (pintype "bidirectional"))
      (node (ref "C501") (pin "1") (pinfunction "1_1") (pintype "bidirectional"))
      (node (ref "C502") (pin "2") (pinfunction "2_2") (pintype "bidirectional"))
      (node (ref "C503") (pin "1") (pinfunction "1_1") (pintype "bidirectional"))
      (node (ref "C504") (pin "1") (pinfunction "1_1") (pintype "bidirectional"))
      (node (ref "C505") (pin "1") (pinfunction "1_1") (pintype "bidirectional"))
      (node (ref "C506") (pin "1") (pinfunction "1_1") (pintype "bidirectional"))
      (node (ref "C507") (pin "2") (pinfunction "2_2") (pintype "bidirectional"))
      (node (ref "C508") (pin "2") (pinfunction "2_2") (pintype "bidirectional"))
      (node (ref "C509") (pin "2") (pinfunction "2_2") (pintype "bidirectional"))
      (node (ref "C510") (pin "1") (pinfunction "1_1") (pintype "bidirectional"))
      (node (ref "C511") (pin "1") (pinfunction "1_1") (pintype "bidirectional"))
      (node (ref "C512") (pin "1") (pinfunction "1_1") (pintype "bidirectional"))
      (node (ref "C513") (pin "1") (pinfunction "1_1") (pintype "bidirectional"))
      (node (ref "C601") (pin "1") (pinfunction "1_1") (pintype "bidirectional"))
      (node (ref "C602") (pin "1") (pinfunction "1_1") (pintype "bidirectional"))
      (node (ref "D201") (pin "1") (pinfunction "1_1") (pintype "bidirectional"))
      (node (ref "D202") (pin "1") (pinfunction "1_1") (pintype "bidirectional"))
      (node (ref "D203") (pin "1") (pinfunction "1_1") (pintype "bidirectional"))
      (node (ref "GND") (pin "1") (pinfunction "P$1_1") (pintype "bidirectional"))
      (node (ref "GND1") (pin "1") (pinfunction "P$1_1") (pintype "bidirectional"))
      (node (ref "GND2") (pin "1") (pinfunction "P$1_1") (pintype "bidirectional"))
      (node (ref "J201") (pin "1@GND") (pinfunction "GND_1@GND") (pintype "passive"))
      (node (ref "J201") (pin "2@GND") (pinfunction "GND_2@GND") (pintype "passive"))
      (node (ref "J201") (pin "GND") (pinfunction "GND_GND") (pintype "passive"))
      (node (ref "J202") (pin "1@GND") (pinfunction "GND_1@GND") (pintype "passive"))
      (node (ref "J202") (pin "2@GND") (pinfunction "GND_2@GND") (pintype "passive"))
      (node (ref "J202") (pin "GND") (pinfunction "GND_GND") (pintype "passive"))
      (node (ref "J301") (pin "5") (pinfunction "5_5") (pintype "bidirectional"))
      (node (ref "J301") (pin "M1") (pinfunction "M_M1") (pintype "bidirectional"))
      (node (ref "J301") (pin "M2") (pinfunction "M_M2") (pintype "bidirectional"))
      (node (ref "J302") (pin "5") (pinfunction "GND_5") (pintype "power_in"))
      (node (ref "J401") (pin "10") (pinfunction "K_10") (pintype "passive"))
      (node (ref "J401") (pin "8") (pinfunction "8(GND)_8") (pintype "bidirectional"))
      (node (ref "J501") (pin "5") (pinfunction "GND_5") (pintype "bidirectional"))
      (node (ref "J501") (pin "M1") (pinfunction "SHIELD_M1") (pintype "bidirectional"))
      (node (ref "J501") (pin "M2") (pinfunction "SHIELD_M2") (pintype "bidirectional"))
      (node (ref "J501") (pin "M3") (pinfunction "SHIELD_M3") (pintype "bidirectional"))
      (node (ref "J501") (pin "M4") (pinfunction "SHIELD_M4") (pintype "bidirectional"))
      (node (ref "J501") (pin "MB1") (pinfunction "SHIELD_MB1") (pintype "bidirectional"))
      (node (ref "J501") (pin "MB2") (pinfunction "SHIELD_MB2") (pintype "bidirectional"))
      (node (ref "J501") (pin "MB3") (pinfunction "SHIELD_MB3") (pintype "bidirectional"))
      (node (ref "J501") (pin "MB4") (pinfunction "SHIELD_MB4") (pintype "bidirectional"))
      (node (ref "J501") (pin "MT1") (pinfunction "SHIELD_MT1") (pintype "bidirectional"))
      (node (ref "J501") (pin "MT2") (pinfunction "SHIELD_MT2") (pintype "bidirectional"))
      (node (ref "J501") (pin "MT3") (pinfunction "SHIELD_MT3") (pintype "bidirectional"))
      (node (ref "J501") (pin "MT4") (pinfunction "SHIELD_MT4") (pintype "bidirectional"))
      (node (ref "LED301") (pin "K") (pinfunction "K_K") (pintype "passive"))
      (node (ref "LED302") (pin "K") (pinfunction "K_K") (pintype "passive"))
      (node (ref "R101") (pin "1") (pinfunction "1_1") (pintype "bidirectional"))
      (node (ref "R103") (pin "2") (pinfunction "2_2") (pintype "bidirectional"))
      (node (ref "R204") (pin "2") (pinfunction "2_2") (pintype "bidirectional"))
      (node (ref "R206") (pin "2") (pinfunction "2_2") (pintype "bidirectional"))
      (node (ref "R210") (pin "2") (pinfunction "2_2") (pintype "bidirectional"))
      (node (ref "R401") (pin "1") (pinfunction "1_1") (pintype "bidirectional"))
      (node (ref "R403") (pin "1") (pinfunction "1_1") (pintype "bidirectional"))
      (node (ref "R414") (pin "1") (pinfunction "1_1") (pintype "bidirectional"))
      (node (ref "R418") (pin "1") (pinfunction "1_1") (pintype "bidirectional"))
      (node (ref "R419") (pin "1") (pinfunction "1_1") (pintype "bidirectional"))
      (node (ref "R502") (pin "1") (pinfunction "1_1") (pintype "bidirectional"))
      (node (ref "R503") (pin "1") (pinfunction "1_1") (pintype "bidirectional"))
      (node (ref "RT201") (pin "1") (pinfunction "1_1") (pintype "bidirectional"))
      (node (ref "S301") (pin "1") (pinfunction "GND1_1") (pintype "passive"))
      (node (ref "S301") (pin "3") (pinfunction "3_3") (pintype "passive"))
      (node (ref "S301") (pin "4") (pinfunction "GND_4") (pintype "passive"))
      (node (ref "U101") (pin "15") (pinfunction "GND_15") (pintype "bidirectional"))
      (node (ref "U101") (pin "24") (pinfunction "GND_24") (pintype "bidirectional"))
      (node (ref "U101") (pin "25") (pinfunction "GND_25") (pintype "bidirectional"))
      (node (ref "U101") (pin "39") (pinfunction "GND_39") (pintype "bidirectional"))
      (node (ref "U101") (pin "46") (pinfunction "GND_46") (pintype "bidirectional"))
      (node (ref "U101") (pin "55") (pinfunction "GND_55") (pintype "bidirectional"))
      (node (ref "U101") (pin "6") (pinfunction "GND_6") (pintype "bidirectional"))
      (node (ref "U101") (pin "62") (pinfunction "GND_62") (pintype "bidirectional"))
      (node (ref "U101") (pin "69") (pinfunction "GND_69") (pintype "bidirectional"))
      (node (ref "U101") (pin "9") (pinfunction "GND_9") (pintype "bidirectional"))
      (node (ref "U201") (pin "20") (pinfunction "GND_20") (pintype "bidirectional"))
      (node (ref "U201") (pin "25") (pinfunction "GND_25") (pintype "bidirectional"))
      (node (ref "U201") (pin "7") (pinfunction "GND_7") (pintype "bidirectional"))
      (node (ref "U202") (pin "20") (pinfunction "GND_20") (pintype "bidirectional"))
      (node (ref "U202") (pin "25") (pinfunction "GND_25") (pintype "bidirectional"))
      (node (ref "U202") (pin "7") (pinfunction "GND_7") (pintype "bidirectional"))
      (node (ref "U203") (pin "2") (pinfunction "GND_2") (pintype "bidirectional"))
      (node (ref "U203") (pin "3") (pinfunction "GND_3") (pintype "bidirectional"))
      (node (ref "U203") (pin "5") (pinfunction "GND_5") (pintype "bidirectional"))
      (node (ref "U204") (pin "2") (pinfunction "GND_2") (pintype "bidirectional"))
      (node (ref "U204") (pin "3") (pinfunction "GND_3") (pintype "bidirectional"))
      (node (ref "U204") (pin "5") (pinfunction "GND_5") (pintype "bidirectional"))
      (node (ref "U205") (pin "10") (pinfunction "GND_10") (pintype "bidirectional"))
      (node (ref "U205") (pin "12") (pinfunction "GND_12") (pintype "bidirectional"))
      (node (ref "U205") (pin "17") (pinfunction "GND_17") (pintype "bidirectional"))
      (node (ref "U206") (pin "2") (pinfunction "GND_2") (pintype "bidirectional"))
      (node (ref "U206") (pin "3") (pinfunction "GND_3") (pintype "bidirectional"))
      (node (ref "U206") (pin "5") (pinfunction "GND_5") (pintype "bidirectional"))
      (node (ref "U207") (pin "2") (pinfunction "GND_2") (pintype "bidirectional"))
      (node (ref "U301") (pin "1") (pinfunction "GND_1") (pintype "bidirectional"))
      (node (ref "U301") (pin "15") (pinfunction "GND_15") (pintype "bidirectional"))
      (node (ref "U301") (pin "38") (pinfunction "GND_38") (pintype "bidirectional"))
      (node (ref "U301") (pin "PAD") (pinfunction "PAD_PAD") (pintype "bidirectional"))
      (node (ref "U401") (pin "33") (pinfunction "GND_33") (pintype "bidirectional"))
      (node (ref "U501") (pin "2") (pinfunction "GND_2") (pintype "bidirectional"))
      (node (ref "U502") (pin "2") (pinfunction "GND_2") (pintype "bidirectional"))
      (node (ref "U503") (pin "3") (pinfunction "GND_3") (pintype "bidirectional"))
      (node (ref "U503") (pin "7") (pinfunction "GND_7") (pintype "bidirectional"))
      (node (ref "U601") (pin "1") (pinfunction "GND_1") (pintype "bidirectional"))
      (node (ref "X201") (pin "2") (pinfunction "GND_2") (pintype "bidirectional"))
      (node (ref "X401") (pin "2") (pinfunction "1_2") (pintype "bidirectional"))
      (node (ref "X401") (pin "4") (pinfunction "1_4") (pintype "bidirectional"))
    )
    (net (code "24") (name "IO0{slash}~{BOOT}") (class "Default")
      (node (ref "ESP-!BOOT!") (pin "1") (pinfunction "P$1_1") (pintype "bidirectional"))
      (node (ref "J302") (pin "2") (pinfunction "GPIO0_2") (pintype "bidirectional"))
      (node (ref "Q601") (pin "3") (pinfunction "C_3") (pintype "passive"))
      (node (ref "R304") (pin "2") (pinfunction "2_2") (pintype "bidirectional"))
      (node (ref "R402") (pin "1") (pinfunction "1_1") (pintype "bidirectional"))
      (node (ref "U301") (pin "25") (pinfunction "IO0_25") (pintype "bidirectional"))
    )
    (net (code "25") (name "LED0{slash}PHYAD0") (class "Default")
      (node (ref "R415") (pin "2") (pinfunction "2_2") (pintype "bidirectional"))
      (node (ref "R417") (pin "2") (pinfunction "2_2") (pintype "bidirectional"))
      (node (ref "U401") (pin "11") (pinfunction "LED0/PHY_AD0_11") (pintype "bidirectional"))
    )
    (net (code "26") (name "LED3{slash}PHYAD3") (class "Default")
      (node (ref "R416") (pin "2") (pinfunction "2_2") (pintype "bidirectional"))
      (node (ref "R418") (pin "2") (pinfunction "2_2") (pintype "bidirectional"))
      (node (ref "U401") (pin "12") (pinfunction "LED3/PHY_AD3_12") (pintype "bidirectional"))
    )
    (net (code "27") (name "LED_GREEN") (class "Default")
      (node (ref "R302") (pin "1") (pinfunction "1_1") (pintype "bidirectional"))
      (node (ref "U301") (pin "28") (pinfunction "IO17_28") (pintype "bidirectional"))
    )
    (net (code "28") (name "LED_RED") (class "Default")
      (node (ref "R303") (pin "1") (pinfunction "1_1") (pintype "bidirectional"))
      (node (ref "U301") (pin "27") (pinfunction "IO16_27") (pintype "bidirectional"))
    )
    (net (code "29") (name "Net-(ANT201-1)") (class "Default")
      (node (ref "ANT201") (pin "FEED") (pinfunction "1_FEED") (pintype "bidirectional"))
      (node (ref "C247") (pin "1") (pinfunction "1_1") (pintype "bidirectional"))
      (node (ref "L214") (pin "2") (pinfunction "2_2") (pintype "bidirectional"))
    )
    (net (code "30") (name "Net-(ANT202-1)") (class "Default")
      (node (ref "ANT202") (pin "FEED") (pinfunction "1_FEED") (pintype "bidirectional"))
      (node (ref "C248") (pin "1") (pinfunction "1_1") (pintype "bidirectional"))
      (node (ref "L215") (pin "2") (pinfunction "2_2") (pintype "bidirectional"))
    )
    (net (code "31") (name "Net-(C205-Pad2)") (class "Default")
      (node (ref "C205") (pin "2") (pinfunction "2_2") (pintype "bidirectional"))
      (node (ref "R201") (pin "2") (pinfunction "2_2") (pintype "bidirectional"))
    )
    (net (code "32") (name "Net-(C207-Pad2)") (class "Default")
      (node (ref "C207") (pin "2") (pinfunction "2_2") (pintype "bidirectional"))
      (node (ref "R202") (pin "2") (pinfunction "2_2") (pintype "bidirectional"))
    )
    (net (code "33") (name "Net-(C218-Pad1)") (class "Default")
      (node (ref "C218") (pin "1") (pinfunction "1_1") (pintype "bidirectional"))
      (node (ref "C219") (pin "2") (pinfunction "2_2") (pintype "bidirectional"))
      (node (ref "C220") (pin "2") (pinfunction "2_2") (pintype "bidirectional"))
      (node (ref "L206") (pin "2") (pinfunction "2_2") (pintype "bidirectional"))
    )
    (net (code "34") (name "Net-(C220-Pad1)") (class "Default")
      (node (ref "C220") (pin "1") (pinfunction "1_1") (pintype "bidirectional"))
      (node (ref "L207") (pin "1") (pinfunction "1_1") (pintype "bidirectional"))
    )
    (net (code "35") (name "Net-(C223-Pad1)") (class "Default")
      (node (ref "C223") (pin "1") (pinfunction "1_1") (pintype "bidirectional"))
      (node (ref "R205") (pin "2") (pinfunction "2_2") (pintype "bidirectional"))
      (node (ref "R206") (pin "1") (pinfunction "1_1") (pintype "bidirectional"))
    )
    (net (code "36") (name "Net-(C235-Pad2)") (class "Default")
      (node (ref "C235") (pin "2") (pinfunction "2_2") (pintype "bidirectional"))
      (node (ref "C238") (pin "1") (pinfunction "1_1") (pintype "bidirectional"))
      (node (ref "L210") (pin "2") (pinfunction "2_2") (pintype "bidirectional"))
      (node (ref "L212") (pin "1") (pinfunction "1_1") (pintype "bidirectional"))
    )
    (net (code "37") (name "Net-(C239-Pad1)") (class "Default")
      (node (ref "C239") (pin "1") (pinfunction "1_1") (pintype "bidirectional"))
      (node (ref "C240") (pin "1") (pinfunction "1_1") (pintype "bidirectional"))
      (node (ref "L211") (pin "2") (pinfunction "2_2") (pintype "bidirectional"))
      (node (ref "L213") (pin "1") (pinfunction "1_1") (pintype "bidirectional"))
    )
    (net (code "38") (name "Net-(C241-Pad1)") (class "Default")
      (node (ref "C241") (pin "1") (pinfunction "1_1") (pintype "bidirectional"))
      (node (ref "C244") (pin "1") (pinfunction "1_1") (pintype "bidirectional"))
      (node (ref "L214") (pin "1") (pinfunction "1_1") (pintype "bidirectional"))
    )
    (net (code "39") (name "Net-(C242-Pad1)") (class "Default")
      (node (ref "C242") (pin "1") (pinfunction "1_1") (pintype "bidirectional"))
      (node (ref "C245") (pin "1") (pinfunction "1_1") (pintype "bidirectional"))
      (node (ref "L215") (pin "1") (pinfunction "1_1") (pintype "bidirectional"))
    )
    (net (code "40") (name "Net-(C243-Pad1)") (class "Default")
      (node (ref "C243") (pin "1") (pinfunction "1_1") (pintype "bidirectional"))
      (node (ref "C246") (pin "1") (pinfunction "1_1") (pintype "bidirectional"))
      (node (ref "L212") (pin "2") (pinfunction "2_2") (pintype "bidirectional"))
    )
    (net (code "41") (name "Net-(C246-Pad2)") (class "Default")
      (node (ref "C246") (pin "2") (pinfunction "2_2") (pintype "bidirectional"))
      (node (ref "C249") (pin "2") (pinfunction "2_2") (pintype "bidirectional"))
      (node (ref "D201") (pin "2") (pinfunction "2_2") (pintype "bidirectional"))
    )
    (net (code "42") (name "Net-(C506-Pad2)") (class "Default")
      (node (ref "C506") (pin "2") (pinfunction "2_2") (pintype "bidirectional"))
      (node (ref "C508") (pin "1") (pinfunction "1_1") (pintype "bidirectional"))
      (node (ref "FB502") (pin "1") (pinfunction "1_1") (pintype "bidirectional"))
      (node (ref "L501") (pin "2") (pinfunction "2_2") (pintype "bidirectional"))
      (node (ref "R504") (pin "2") (pinfunction "2_2") (pintype "bidirectional"))
    )
    (net (code "43") (name "Net-(C507-Pad1)") (class "Default")
      (node (ref "C507") (pin "1") (pinfunction "1_1") (pintype "bidirectional"))
      (node (ref "C509") (pin "1") (pinfunction "1_1") (pintype "bidirectional"))
      (node (ref "FB503") (pin "1") (pinfunction "1_1") (pintype "bidirectional"))
      (node (ref "FB504") (pin "1") (pinfunction "1_1") (pintype "bidirectional"))
      (node (ref "L502") (pin "2") (pinfunction "2_2") (pintype "bidirectional"))
      (node (ref "R505") (pin "2") (pinfunction "2_2") (pintype "bidirectional"))
    )
    (net (code "44") (name "Net-(ESP-VCC-P$1)") (class "Default")
      (node (ref "C301") (pin "2") (pinfunction "2_2") (pintype "bidirectional"))
      (node (ref "C302") (pin "2") (pinfunction "2_2") (pintype "bidirectional"))
      (node (ref "ESP-VCC") (pin "1") (pinfunction "P$1_1") (pintype "bidirectional"))
      (node (ref "FB301") (pin "1") (pinfunction "1_1") (pintype "bidirectional"))
      (node (ref "R301") (pin "1") (pinfunction "1_1") (pintype "bidirectional"))
      (node (ref "U301") (pin "2") (pinfunction "3V3_2") (pintype "bidirectional"))
    )
    (net (code "45") (name "Net-(J201-SIGNAL)") (class "Default")
      (node (ref "C236") (pin "2") (pinfunction "2_2") (pintype "bidirectional"))
      (node (ref "D202") (pin "2") (pinfunction "2_2") (pintype "bidirectional"))
      (node (ref "J201") (pin "ANT") (pinfunction "SIGNAL_ANT") (pintype "passive"))
    )
    (net (code "46") (name "Net-(J202-SIGNAL)") (class "Default")
      (node (ref "C237") (pin "2") (pinfunction "2_2") (pintype "bidirectional"))
      (node (ref "D203") (pin "2") (pinfunction "2_2") (pintype "bidirectional"))
      (node (ref "J202") (pin "ANT") (pinfunction "SIGNAL_ANT") (pintype "passive"))
    )
    (net (code "47") (name "Net-(J401A-CRD)") (class "Default")
      (node (ref "C415") (pin "2") (pinfunction "2_2") (pintype "bidirectional"))
      (node (ref "J401") (pin "5") (pinfunction "CRD_5") (pintype "bidirectional"))
    )
    (net (code "48") (name "Net-(J401A-CTD)") (class "Default")
      (node (ref "C414") (pin "2") (pinfunction "2_2") (pintype "bidirectional"))
      (node (ref "J401") (pin "4") (pinfunction "CTD_4") (pintype "bidirectional"))
    )
    (net (code "49") (name "Net-(J401A-SHIELD1)") (class "Default")
      (node (ref "C416") (pin "2") (pinfunction "2_2") (pintype "bidirectional"))
      (node (ref "J401") (pin "Z1") (pinfunction "SHIELD1_Z1") (pintype "power_in"))
      (node (ref "J401") (pin "Z2") (pinfunction "SHIELD2_Z2") (pintype "power_in"))
      (node (ref "R419") (pin "2") (pinfunction "2_2") (pintype "bidirectional"))
    )
    (net (code "50") (name "Net-(J401B-A)") (class "Default")
      (node (ref "J401") (pin "9") (pinfunction "A_9") (pintype "passive"))
      (node (ref "R416") (pin "1") (pinfunction "1_1") (pintype "bidirectional"))
    )
    (net (code "51") (name "Net-(J401C-K)") (class "Default")
      (node (ref "J401") (pin "12") (pinfunction "K_12") (pintype "passive"))
      (node (ref "R415") (pin "1") (pinfunction "1_1") (pintype "bidirectional"))
    )
    (net (code "52") (name "Net-(J501-DN)") (class "Default")
      (node (ref "J501") (pin "2") (pinfunction "DN_2") (pintype "bidirectional"))
      (node (ref "SJ501") (pin "1") (pinfunction "1_1") (pintype "passive"))
      (node (ref "USB-DN") (pin "1") (pinfunction "P$1_1") (pintype "bidirectional"))
    )
    (net (code "53") (name "Net-(J501-DP)") (class "Default")
      (node (ref "J501") (pin "3") (pinfunction "DP_3") (pintype "bidirectional"))
      (node (ref "SJ502") (pin "1") (pinfunction "1_1") (pintype "passive"))
      (node (ref "USB-DP") (pin "1") (pinfunction "P$1_1") (pintype "bidirectional"))
    )
    (net (code "54") (name "Net-(LED301-PadA)") (class "Default")
      (node (ref "LED301") (pin "A") (pinfunction "A_A") (pintype "passive"))
      (node (ref "R302") (pin "2") (pinfunction "2_2") (pintype "bidirectional"))
    )
    (net (code "55") (name "Net-(LED302-PadA)") (class "Default")
      (node (ref "LED302") (pin "A") (pinfunction "A_A") (pintype "passive"))
      (node (ref "R303") (pin "2") (pinfunction "2_2") (pintype "bidirectional"))
    )
    (net (code "56") (name "Net-(PHY-TEST-P$1)") (class "Default")
      (node (ref "PHY-TEST") (pin "1") (pinfunction "P$1_1") (pintype "bidirectional"))
      (node (ref "U401") (pin "24") (pinfunction "TEST_ON_24") (pintype "bidirectional"))
    )
    (net (code "57") (name "Net-(PPS-P$1)") (class "Default")
      (node (ref "PPS") (pin "1") (pinfunction "P$1_1") (pintype "bidirectional"))
      (node (ref "U101") (pin "8") (pinfunction "PPS_8") (pintype "bidirectional"))
    )
    (net (code "58") (name "Net-(Q601-B)") (class "Default")
      (node (ref "Q601") (pin "1") (pinfunction "B_1") (pintype "passive"))
      (node (ref "R601") (pin "1") (pinfunction "1_1") (pintype "bidirectional"))
    )
    (net (code "59") (name "Net-(Q602-B)") (class "Default")
      (node (ref "Q602") (pin "1") (pinfunction "B_1") (pintype "passive"))
      (node (ref "R602") (pin "1") (pinfunction "1_1") (pintype "bidirectional"))
    )
    (net (code "60") (name "Net-(U101-HOST_MISO)") (class "Default")
      (node (ref "R102") (pin "2") (pinfunction "2_2") (pintype "bidirectional"))
      (node (ref "U101") (pin "2") (pinfunction "HOST_MISO_2") (pintype "bidirectional"))
    )
    (net (code "61") (name "Net-(U101-RADIO_A_CLK_I)") (class "Default")
      (node (ref "R106") (pin "2") (pinfunction "2_2") (pintype "bidirectional"))
      (node (ref "U101") (pin "43") (pinfunction "RADIO_A_CLK_I_43") (pintype "bidirectional"))
    )
    (net (code "62") (name "Net-(U101-RADIO_A_IQ_0)") (class "Default")
      (node (ref "R107") (pin "2") (pinfunction "2_2") (pintype "bidirectional"))
      (node (ref "U101") (pin "44") (pinfunction "RADIO_A_IQ_0_44") (pintype "bidirectional"))
    )
    (net (code "63") (name "Net-(U101-RADIO_A_IQ_1)") (class "Default")
      (node (ref "R108") (pin "2") (pinfunction "2_2") (pintype "bidirectional"))
      (node (ref "U101") (pin "45") (pinfunction "RADIO_A_IQ_1_45") (pintype "bidirectional"))
    )
    (net (code "64") (name "Net-(U101-RADIO_A_IQ_2)") (class "Default")
      (node (ref "R109") (pin "2") (pinfunction "2_2") (pintype "bidirectional"))
      (node (ref "U101") (pin "49") (pinfunction "RADIO_A_IQ_2_49") (pintype "bidirectional"))
    )
    (net (code "65") (name "Net-(U101-RADIO_A_IQ_3)") (class "Default")
      (node (ref "R110") (pin "2") (pinfunction "2_2") (pintype "bidirectional"))
      (node (ref "U101") (pin "41") (pinfunction "RADIO_A_IQ_3_41") (pintype "bidirectional"))
    )
    (net (code "66") (name "Net-(U101-RADIO_A_IQ_4)") (class "Default")
      (node (ref "R111") (pin "2") (pinfunction "2_2") (pintype "bidirectional"))
      (node (ref "U101") (pin "48") (pinfunction "RADIO_A_IQ_4_48") (pintype "bidirectional"))
    )
    (net (code "67") (name "Net-(U101-RADIO_B_CLK_I)") (class "Default")
      (node (ref "R112") (pin "2") (pinfunction "2_2") (pintype "bidirectional"))
      (node (ref "U101") (pin "34") (pinfunction "RADIO_B_CLK_I_34") (pintype "bidirectional"))
    )
    (net (code "68") (name "Net-(U101-RADIO_B_IQ_0)") (class "Default")
      (node (ref "R113") (pin "2") (pinfunction "2_2") (pintype "bidirectional"))
      (node (ref "U101") (pin "35") (pinfunction "RADIO_B_IQ_0_35") (pintype "bidirectional"))
    )
    (net (code "69") (name "Net-(U101-RADIO_B_IQ_1)") (class "Default")
      (node (ref "R114") (pin "2") (pinfunction "2_2") (pintype "bidirectional"))
      (node (ref "U101") (pin "36") (pinfunction "RADIO_B_IQ_1_36") (pintype "bidirectional"))
    )
    (net (code "70") (name "Net-(U101-RADIO_B_IQ_2)") (class "Default")
      (node (ref "R115") (pin "2") (pinfunction "2_2") (pintype "bidirectional"))
      (node (ref "U101") (pin "38") (pinfunction "RADIO_B_IQ_2_38") (pintype "bidirectional"))
    )
    (net (code "71") (name "Net-(U101-RADIO_B_IQ_3)") (class "Default")
      (node (ref "R116") (pin "2") (pinfunction "2_2") (pintype "bidirectional"))
      (node (ref "U101") (pin "32") (pinfunction "RADIO_B_IQ_3_32") (pintype "bidirectional"))
    )
    (net (code "72") (name "Net-(U101-RADIO_B_IQ_4)") (class "Default")
      (node (ref "R117") (pin "2") (pinfunction "2_2") (pintype "bidirectional"))
      (node (ref "U101") (pin "37") (pinfunction "RADIO_B_IQ_4_37") (pintype "bidirectional"))
    )
    (net (code "73") (name "Net-(U101-SP_VALID)") (class "Default")
      (node (ref "R103") (pin "1") (pinfunction "1_1") (pintype "bidirectional"))
      (node (ref "U101") (pin "20") (pinfunction "SP_VALID_20") (pintype "bidirectional"))
    )
    (net (code "74") (name "Net-(U201-DCC_SW)") (class "Default")
      (node (ref "L201") (pin "2") (pinfunction "2_2") (pintype "bidirectional"))
      (node (ref "U201") (pin "8") (pinfunction "DCC_SW_8") (pintype "bidirectional"))
    )
    (net (code "75") (name "Net-(U201-RFI_N)") (class "Default")
      (node (ref "C215") (pin "1") (pinfunction "1_1") (pintype "bidirectional"))
      (node (ref "L204") (pin "1") (pinfunction "1_1") (pintype "bidirectional"))
      (node (ref "U201") (pin "23") (pinfunction "RFI_N_23") (pintype "bidirectional"))
    )
    (net (code "76") (name "Net-(U201-RFI_P)") (class "Default")
      (node (ref "C213") (pin "2") (pinfunction "2_2") (pintype "bidirectional"))
      (node (ref "L204") (pin "2") (pinfunction "2_2") (pintype "bidirectional"))
      (node (ref "U201") (pin "22") (pinfunction "RFI_P_22") (pintype "bidirectional"))
    )
    (net (code "77") (name "Net-(U201-RFO)") (class "Default")
      (node (ref "C218") (pin "2") (pinfunction "2_2") (pintype "bidirectional"))
      (node (ref "L205") (pin "1") (pinfunction "1_1") (pintype "bidirectional"))
      (node (ref "L206") (pin "1") (pinfunction "1_1") (pintype "bidirectional"))
      (node (ref "U201") (pin "24") (pinfunction "RFO_24") (pintype "bidirectional"))
    )
    (net (code "78") (name "Net-(U201-VREG)") (class "Default")
      (node (ref "C203") (pin "2") (pinfunction "2_2") (pintype "bidirectional"))
      (node (ref "FB201") (pin "2") (pinfunction "2_2") (pintype "bidirectional"))
      (node (ref "L201") (pin "1") (pinfunction "1_1") (pintype "bidirectional"))
      (node (ref "U201") (pin "6") (pinfunction "VREG_6") (pintype "bidirectional"))
    )
    (net (code "79") (name "Net-(U201-VR_PA)") (class "Default")
      (node (ref "C210") (pin "2") (pinfunction "2_2") (pintype "bidirectional"))
      (node (ref "C211") (pin "2") (pinfunction "2_2") (pintype "bidirectional"))
      (node (ref "L205") (pin "2") (pinfunction "2_2") (pintype "bidirectional"))
      (node (ref "U201") (pin "1") (pinfunction "VR_PA_1") (pintype "bidirectional"))
    )
    (net (code "80") (name "Net-(U201-XTA)") (class "Default")
      (node (ref "C205") (pin "1") (pinfunction "1_1") (pintype "bidirectional"))
      (node (ref "U201") (pin "3") (pinfunction "XTA_3") (pintype "bidirectional"))
    )
    (net (code "81") (name "Net-(U202-DCC_SW)") (class "Default")
      (node (ref "L202") (pin "2") (pinfunction "2_2") (pintype "bidirectional"))
      (node (ref "U202") (pin "8") (pinfunction "DCC_SW_8") (pintype "bidirectional"))
    )
    (net (code "82") (name "Net-(U202-RFI_N)") (class "Default")
      (node (ref "C214") (pin "1") (pinfunction "1_1") (pintype "bidirectional"))
      (node (ref "L203") (pin "1") (pinfunction "1_1") (pintype "bidirectional"))
      (node (ref "U202") (pin "23") (pinfunction "RFI_N_23") (pintype "bidirectional"))
    )
    (net (code "83") (name "Net-(U202-RFI_P)") (class "Default")
      (node (ref "C212") (pin "2") (pinfunction "2_2") (pintype "bidirectional"))
      (node (ref "L203") (pin "2") (pinfunction "2_2") (pintype "bidirectional"))
      (node (ref "U202") (pin "22") (pinfunction "RFI_P_22") (pintype "bidirectional"))
    )
    (net (code "84") (name "Net-(U202-VREG)") (class "Default")
      (node (ref "C204") (pin "2") (pinfunction "2_2") (pintype "bidirectional"))
      (node (ref "FB202") (pin "2") (pinfunction "2_2") (pintype "bidirectional"))
      (node (ref "L202") (pin "1") (pinfunction "1_1") (pintype "bidirectional"))
      (node (ref "U202") (pin "6") (pinfunction "VREG_6") (pintype "bidirectional"))
    )
    (net (code "85") (name "Net-(U202-XTA)") (class "Default")
      (node (ref "C207") (pin "1") (pinfunction "1_1") (pintype "bidirectional"))
      (node (ref "U202") (pin "3") (pinfunction "XTA_3") (pintype "bidirectional"))
    )
    (net (code "86") (name "Net-(U203-IN)") (class "Default")
      (node (ref "C224") (pin "1") (pinfunction "1_1") (pintype "bidirectional"))
      (node (ref "U203") (pin "1") (pinfunction "IN_1") (pintype "bidirectional"))
    )
    (net (code "87") (name "Net-(U203-OUT)") (class "Default")
      (node (ref "C214") (pin "2") (pinfunction "2_2") (pintype "bidirectional"))
      (node (ref "C215") (pin "2") (pinfunction "2_2") (pintype "bidirectional"))
      (node (ref "C216") (pin "2") (pinfunction "2_2") (pintype "bidirectional"))
      (node (ref "C217") (pin "2") (pinfunction "2_2") (pintype "bidirectional"))
      (node (ref "U203") (pin "4") (pinfunction "OUT_4") (pintype "bidirectional"))
    )
    (net (code "88") (name "Net-(U204-IN)") (class "Default")
      (node (ref "C221") (pin "2") (pinfunction "2_2") (pintype "bidirectional"))
      (node (ref "L207") (pin "2") (pinfunction "2_2") (pintype "bidirectional"))
      (node (ref "U204") (pin "1") (pinfunction "IN_1") (pintype "bidirectional"))
    )
    (net (code "89") (name "Net-(U204-OUT)") (class "Default")
      (node (ref "R204") (pin "1") (pinfunction "1_1") (pintype "bidirectional"))
      (node (ref "R205") (pin "1") (pinfunction "1_1") (pintype "bidirectional"))
      (node (ref "U204") (pin "4") (pinfunction "OUT_4") (pintype "bidirectional"))
    )
    (net (code "90") (name "Net-(U205-ANT)") (class "Default")
      (node (ref "C233") (pin "1") (pinfunction "1_1") (pintype "bidirectional"))
      (node (ref "C235") (pin "1") (pinfunction "1_1") (pintype "bidirectional"))
      (node (ref "L210") (pin "1") (pinfunction "1_1") (pintype "bidirectional"))
      (node (ref "U205") (pin "9") (pinfunction "ANT_9") (pintype "bidirectional"))
    )
    (net (code "91") (name "Net-(U205-LNA_IN)") (class "Default")
      (node (ref "U205") (pin "7") (pinfunction "LNA_IN_7") (pintype "bidirectional"))
      (node (ref "U206") (pin "4") (pinfunction "OUT_4") (pintype "bidirectional"))
    )
    (net (code "92") (name "Net-(U205-PA_OUT)") (class "Default")
      (node (ref "L209") (pin "1") (pinfunction "1_1") (pintype "bidirectional"))
      (node (ref "L213") (pin "2") (pinfunction "2_2") (pintype "bidirectional"))
      (node (ref "U205") (pin "13") (pinfunction "PA_OUT_13") (pintype "bidirectional"))
    )
    (net (code "93") (name "Net-(U205-RX)") (class "Default")
      (node (ref "C224") (pin "2") (pinfunction "2_2") (pintype "bidirectional"))
      (node (ref "U205") (pin "2") (pinfunction "RX_2") (pintype "bidirectional"))
    )
    (net (code "94") (name "Net-(U205-RX_FLT)") (class "Default")
      (node (ref "U205") (pin "8") (pinfunction "RX_FLT_8") (pintype "bidirectional"))
      (node (ref "U206") (pin "1") (pinfunction "IN_1") (pintype "bidirectional"))
    )
    (net (code "95") (name "Net-(U205-TX)") (class "Default")
      (node (ref "C223") (pin "2") (pinfunction "2_2") (pintype "bidirectional"))
      (node (ref "U205") (pin "1") (pinfunction "TX_1") (pintype "bidirectional"))
    )
    (net (code "96") (name "Net-(U205-TX_IN)") (class "Default")
      (node (ref "C234") (pin "1") (pinfunction "1_1") (pintype "bidirectional"))
      (node (ref "L211") (pin "1") (pinfunction "1_1") (pintype "bidirectional"))
      (node (ref "U205") (pin "11") (pinfunction "TX_IN_11") (pintype "bidirectional"))
    )
    (net (code "97") (name "Net-(U205-VCC1)") (class "Default")
      (node (ref "L208") (pin "1") (pinfunction "1_1") (pintype "bidirectional"))
      (node (ref "U205") (pin "16") (pinfunction "VCC1_16") (pintype "bidirectional"))
    )
    (net (code "98") (name "Net-(U207-CTL)") (class "Default")
      (node (ref "C250") (pin "2") (pinfunction "2_2") (pintype "bidirectional"))
      (node (ref "R214") (pin "2") (pinfunction "2_2") (pintype "bidirectional"))
      (node (ref "U207") (pin "4") (pinfunction "CTL_4") (pintype "bidirectional"))
    )
    (net (code "99") (name "Net-(U207-RFC)") (class "Default")
      (node (ref "C249") (pin "1") (pinfunction "1_1") (pintype "bidirectional"))
      (node (ref "U207") (pin "5") (pinfunction "RFC_5") (pintype "bidirectional"))
    )
    (net (code "100") (name "Net-(U401-AVDD33)") (class "Default")
      (node (ref "C406") (pin "2") (pinfunction "2_2") (pintype "bidirectional"))
      (node (ref "C407") (pin "2") (pinfunction "2_2") (pintype "bidirectional"))
      (node (ref "FB401") (pin "1") (pinfunction "1_1") (pintype "bidirectional"))
      (node (ref "U401") (pin "31") (pinfunction "AVDD33_31") (pintype "bidirectional"))
    )
    (net (code "101") (name "Net-(U401-COL{slash}RMII)") (class "Default")
      (node (ref "R411") (pin "1") (pinfunction "1_1") (pintype "bidirectional"))
      (node (ref "U401") (pin "4") (pinfunction "COL/RMII_4") (pintype "bidirectional"))
    )
    (net (code "102") (name "Net-(U401-CRS{slash}LEDMOD)") (class "Default")
      (node (ref "R412") (pin "1") (pinfunction "1_1") (pintype "bidirectional"))
      (node (ref "U401") (pin "20") (pinfunction "CRS/LEDMOD_20") (pintype "bidirectional"))
    )
    (net (code "103") (name "Net-(U401-ISET)") (class "Default")
      (node (ref "R414") (pin "2") (pinfunction "2_2") (pintype "bidirectional"))
      (node (ref "U401") (pin "25") (pinfunction "ISET_25") (pintype "bidirectional"))
    )
    (net (code "104") (name "Net-(U401-REGOUT)") (class "Default")
      (node (ref "C402") (pin "2") (pinfunction "2_2") (pintype "bidirectional"))
      (node (ref "C403") (pin "2") (pinfunction "2_2") (pintype "bidirectional"))
      (node (ref "U401") (pin "28") (pinfunction "REGOUT_28") (pintype "bidirectional"))
    )
    (net (code "105") (name "Net-(U401-RXCLK{slash}50M_OUT)") (class "Default")
      (node (ref "R406") (pin "2") (pinfunction "2_2") (pintype "bidirectional"))
      (node (ref "U401") (pin "14") (pinfunction "RXCLK/50M_OUT_14") (pintype "bidirectional"))
    )
    (net (code "106") (name "Net-(U401-RXD0)") (class "Default")
      (node (ref "R408") (pin "2") (pinfunction "2_2") (pintype "bidirectional"))
      (node (ref "U401") (pin "18") (pinfunction "RXD0_18") (pintype "bidirectional"))
    )
    (net (code "107") (name "Net-(U401-RXD1)") (class "Default")
      (node (ref "R409") (pin "2") (pinfunction "2_2") (pintype "bidirectional"))
      (node (ref "U401") (pin "17") (pinfunction "RXD1_17") (pintype "bidirectional"))
    )
    (net (code "108") (name "Net-(U401-RXDV{slash}CRS_DV{slash}FX_HEN)") (class "Default")
      (node (ref "R410") (pin "2") (pinfunction "2_2") (pintype "bidirectional"))
      (node (ref "U401") (pin "19") (pinfunction "RXDV/CRS_DV/FX_HEN_19") (pintype "bidirectional"))
    )
    (net (code "109") (name "Net-(U401-RXER{slash}INTR_32)") (class "Default")
      (node (ref "R407") (pin "1") (pinfunction "1_1") (pintype "bidirectional"))
      (node (ref "U401") (pin "21") (pinfunction "RXER/INTR_32_21") (pintype "bidirectional"))
    )
    (net (code "110") (name "Net-(U401-TXCLK{slash}50M_IN)") (class "Default")
      (node (ref "R402") (pin "2") (pinfunction "2_2") (pintype "bidirectional"))
      (node (ref "R406") (pin "1") (pinfunction "1_1") (pintype "bidirectional"))
      (node (ref "U401") (pin "10") (pinfunction "TXCLK/50M_IN_10") (pintype "bidirectional"))
    )
    (net (code "111") (name "Net-(U401-TXD0)") (class "Default")
      (node (ref "R404") (pin "2") (pinfunction "2_2") (pintype "bidirectional"))
      (node (ref "U401") (pin "9") (pinfunction "TXD0_9") (pintype "bidirectional"))
    )
    (net (code "112") (name "Net-(U401-TXD1)") (class "Default")
      (node (ref "R405") (pin "2") (pinfunction "2_2") (pintype "bidirectional"))
      (node (ref "U401") (pin "8") (pinfunction "TXD1_8") (pintype "bidirectional"))
    )
    (net (code "113") (name "Net-(U401-TXER{slash}FXSD)") (class "Default")
      (node (ref "R403") (pin "2") (pinfunction "2_2") (pintype "bidirectional"))
      (node (ref "U401") (pin "1") (pinfunction "TXER/FXSD_1") (pintype "bidirectional"))
    )
    (net (code "114") (name "Net-(U401-X1_XI)") (class "Default")
      (node (ref "C404") (pin "2") (pinfunction "2_2") (pintype "bidirectional"))
      (node (ref "U401") (pin "2") (pinfunction "X1_XI_2") (pintype "bidirectional"))
      (node (ref "X401") (pin "3") (pinfunction "2_3") (pintype "passive"))
    )
    (net (code "115") (name "Net-(U401-X2_XO)") (class "Default")
      (node (ref "C405") (pin "2") (pinfunction "2_2") (pintype "bidirectional"))
      (node (ref "U401") (pin "3") (pinfunction "X2_XO_3") (pintype "bidirectional"))
      (node (ref "X401") (pin "1") (pinfunction "1_1") (pintype "passive"))
    )
    (net (code "116") (name "Net-(U501-FB)") (class "Default")
      (node (ref "R502") (pin "2") (pinfunction "2_2") (pintype "bidirectional"))
      (node (ref "R504") (pin "1") (pinfunction "1_1") (pintype "bidirectional"))
      (node (ref "U501") (pin "5") (pinfunction "FB_5") (pintype "bidirectional"))
    )
    (net (code "117") (name "Net-(U501-SW)") (class "Default")
      (node (ref "L501") (pin "1") (pinfunction "1_1") (pintype "bidirectional"))
      (node (ref "U501") (pin "3") (pinfunction "SW_3") (pintype "bidirectional"))
    )
    (net (code "118") (name "Net-(U502-FB)") (class "Default")
      (node (ref "R503") (pin "2") (pinfunction "2_2") (pintype "bidirectional"))
      (node (ref "R505") (pin "1") (pinfunction "1_1") (pintype "bidirectional"))
      (node (ref "U502") (pin "5") (pinfunction "FB_5") (pintype "bidirectional"))
    )
    (net (code "119") (name "Net-(U502-SW)") (class "Default")
      (node (ref "L502") (pin "1") (pinfunction "1_1") (pintype "bidirectional"))
      (node (ref "U502") (pin "3") (pinfunction "SW_3") (pintype "bidirectional"))
    )
    (net (code "120") (name "Net-(U503-FB)") (class "Default")
      (node (ref "C505") (pin "2") (pinfunction "2_2") (pintype "bidirectional"))
      (node (ref "FB501") (pin "1") (pinfunction "1_1") (pintype "bidirectional"))
      (node (ref "U503") (pin "1") (pinfunction "OUT_1") (pintype "bidirectional"))
      (node (ref "U503") (pin "2") (pinfunction "FB_2") (pintype "bidirectional"))
    )
    (net (code "121") (name "Net-(X201-E{slash}NC)") (class "Default")
      (node (ref "R210") (pin "1") (pinfunction "1_1") (pintype "bidirectional"))
      (node (ref "R212") (pin "1") (pinfunction "1_1") (pintype "bidirectional"))
      (node (ref "X201") (pin "1") (pinfunction "E/NC_1") (pintype "bidirectional"))
    )
    (net (code "122") (name "Net-(X201-OUT)") (class "Default")
      (node (ref "R211") (pin "1") (pinfunction "1_1") (pintype "bidirectional"))
      (node (ref "X201") (pin "3") (pinfunction "OUT_3") (pintype "bidirectional"))
    )
    (net (code "123") (name "RADIO_A_CLK_32M") (class "Default")
      (node (ref "R106") (pin "1") (pinfunction "1_1") (pintype "bidirectional"))
      (node (ref "U201") (pin "14") (pinfunction "BUSY_14") (pintype "bidirectional"))
    )
    (net (code "124") (name "RADIO_A_CLK_O") (class "Default")
      (node (ref "R111") (pin "1") (pinfunction "1_1") (pintype "bidirectional"))
      (node (ref "U201") (pin "11") (pinfunction "DIO5_11") (pintype "bidirectional"))
    )
    (net (code "125") (name "RADIO_A_IQ_0") (class "Default")
      (node (ref "R107") (pin "1") (pinfunction "1_1") (pintype "bidirectional"))
      (node (ref "U201") (pin "13") (pinfunction "DIO1_13") (pintype "bidirectional"))
    )
    (net (code "126") (name "RADIO_A_IQ_1") (class "Default")
      (node (ref "R108") (pin "1") (pinfunction "1_1") (pintype "bidirectional"))
      (node (ref "U201") (pin "12") (pinfunction "DIO2_12") (pintype "bidirectional"))
    )
    (net (code "127") (name "RADIO_A_IQ_2") (class "Default")
      (node (ref "R109") (pin "1") (pinfunction "1_1") (pintype "bidirectional"))
      (node (ref "U201") (pin "5") (pinfunction "DIO3_5") (pintype "bidirectional"))
    )
    (net (code "128") (name "RADIO_A_IQ_3") (class "Default")
      (node (ref "R110") (pin "1") (pinfunction "1_1") (pintype "bidirectional"))
      (node (ref "U201") (pin "21") (pinfunction "DIO4_21") (pintype "bidirectional"))
    )
    (net (code "129") (name "RADIO_A_MISO") (class "Default")
      (node (ref "U101") (pin "42") (pinfunction "RADIO_A_MISO_42") (pintype "bidirectional"))
      (node (ref "U201") (pin "16") (pinfunction "MISO_16") (pintype "output"))
    )
    (net (code "130") (name "RADIO_A_MOSI") (class "Default")
      (node (ref "U101") (pin "67") (pinfunction "RADIO_A_MOSI_67") (pintype "bidirectional"))
      (node (ref "U201") (pin "17") (pinfunction "MOSI_17") (pintype "input"))
    )
    (net (code "131") (name "RADIO_A_SCK") (class "Default")
      (node (ref "U101") (pin "65") (pinfunction "RADIO_A_SCK_65") (pintype "bidirectional"))
      (node (ref "U201") (pin "18") (pinfunction "SCK_18") (pintype "input"))
    )
    (net (code "132") (name "RADIO_B_CLK_32M") (class "Default")
      (node (ref "R112") (pin "1") (pinfunction "1_1") (pintype "bidirectional"))
      (node (ref "U202") (pin "14") (pinfunction "BUSY_14") (pintype "bidirectional"))
    )
    (net (code "133") (name "RADIO_B_CLK_O") (class "Default")
      (node (ref "R117") (pin "1") (pinfunction "1_1") (pintype "bidirectional"))
      (node (ref "U202") (pin "11") (pinfunction "DIO5_11") (pintype "bidirectional"))
    )
    (net (code "134") (name "RADIO_B_IQ_0") (class "Default")
      (node (ref "R113") (pin "1") (pinfunction "1_1") (pintype "bidirectional"))
      (node (ref "U202") (pin "13") (pinfunction "DIO1_13") (pintype "bidirectional"))
    )
    (net (code "135") (name "RADIO_B_IQ_1") (class "Default")
      (node (ref "R114") (pin "1") (pinfunction "1_1") (pintype "bidirectional"))
      (node (ref "U202") (pin "12") (pinfunction "DIO2_12") (pintype "bidirectional"))
    )
    (net (code "136") (name "RADIO_B_IQ_2") (class "Default")
      (node (ref "R115") (pin "1") (pinfunction "1_1") (pintype "bidirectional"))
      (node (ref "U202") (pin "5") (pinfunction "DIO3_5") (pintype "bidirectional"))
    )
    (net (code "137") (name "RADIO_B_IQ_3") (class "Default")
      (node (ref "R116") (pin "1") (pinfunction "1_1") (pintype "bidirectional"))
      (node (ref "U202") (pin "21") (pinfunction "DIO4_21") (pintype "bidirectional"))
    )
    (net (code "138") (name "RADIO_B_MISO") (class "Default")
      (node (ref "U101") (pin "33") (pinfunction "RADIO_B_MISO_33") (pintype "bidirectional"))
      (node (ref "U202") (pin "16") (pinfunction "MISO_16") (pintype "output"))
    )
    (net (code "139") (name "RADIO_B_MOSI") (class "Default")
      (node (ref "U101") (pin "19") (pinfunction "RADIO_B_MOSI_19") (pintype "bidirectional"))
      (node (ref "U202") (pin "17") (pinfunction "MOSI_17") (pintype "input"))
    )
    (net (code "140") (name "RADIO_B_SCK") (class "Default")
      (node (ref "U101") (pin "21") (pinfunction "RADIO_B_SCK_21") (pintype "bidirectional"))
      (node (ref "U202") (pin "18") (pinfunction "SCK_18") (pintype "input"))
    )
    (net (code "141") (name "RD_N") (class "Default")
      (node (ref "C410") (pin "2") (pinfunction "2_2") (pintype "bidirectional"))
      (node (ref "J401") (pin "6") (pinfunction "RD-_6") (pintype "bidirectional"))
      (node (ref "U401") (pin "26") (pinfunction "MDI_RN_26") (pintype "bidirectional"))
    )
    (net (code "142") (name "RD_P") (class "Default")
      (node (ref "C411") (pin "2") (pinfunction "2_2") (pintype "bidirectional"))
      (node (ref "J401") (pin "3") (pinfunction "RD+_3") (pintype "bidirectional"))
      (node (ref "U401") (pin "27") (pinfunction "MDI_RP_27") (pintype "bidirectional"))
    )
    (net (code "143") (name "REG_EN") (class "Default")
      (node (ref "C504") (pin "2") (pinfunction "2_2") (pintype "bidirectional"))
      (node (ref "R501") (pin "2") (pinfunction "2_2") (pintype "bidirectional"))
      (node (ref "REG-EN") (pin "1") (pinfunction "P$1_1") (pintype "bidirectional"))
      (node (ref "U502") (pin "1") (pinfunction "EN/PG_1") (pintype "bidirectional"))
      (node (ref "U503") (pin "4") (pinfunction "EN_4") (pintype "bidirectional"))
    )
    (net (code "144") (name "RFIO1") (class "Default")
      (node (ref "C236") (pin "1") (pinfunction "1_1") (pintype "bidirectional"))
      (node (ref "C241") (pin "2") (pinfunction "2_2") (pintype "bidirectional"))
      (node (ref "U207") (pin "1") (pinfunction "RF1_1") (pintype "bidirectional"))
    )
    (net (code "145") (name "RFIO2") (class "Default")
      (node (ref "C237") (pin "1") (pinfunction "1_1") (pintype "bidirectional"))
      (node (ref "C242") (pin "2") (pinfunction "2_2") (pintype "bidirectional"))
      (node (ref "U207") (pin "3") (pinfunction "RF2_3") (pintype "bidirectional"))
    )
    (net (code "146") (name "RTS") (class "Default")
      (node (ref "Q602") (pin "2") (pinfunction "E_2") (pintype "passive"))
      (node (ref "R601") (pin "2") (pinfunction "2_2") (pintype "bidirectional"))
      (node (ref "U601") (pin "14") (pinfunction "RTS#_14") (pintype "bidirectional"))
    )
    (net (code "147") (name "SPI_MISO") (class "Default")
      (node (ref "R102") (pin "1") (pinfunction "1_1") (pintype "bidirectional"))
      (node (ref "SX-MISO") (pin "1") (pinfunction "P$1_1") (pintype "bidirectional"))
      (node (ref "U301") (pin "14") (pinfunction "IO12_14") (pintype "bidirectional"))
    )
    (net (code "148") (name "SPI_MOSI") (class "Default")
      (node (ref "SX-MOSI") (pin "1") (pinfunction "P$1_1") (pintype "bidirectional"))
      (node (ref "U101") (pin "3") (pinfunction "HOST_MOSI_3") (pintype "bidirectional"))
      (node (ref "U301") (pin "16") (pinfunction "IO13_16") (pintype "bidirectional"))
    )
    (net (code "149") (name "SPI_SCLK") (class "Default")
      (node (ref "SX-CLK") (pin "1") (pinfunction "P$1_1") (pintype "bidirectional"))
      (node (ref "U101") (pin "4") (pinfunction "HOST_SCK_4") (pintype "bidirectional"))
      (node (ref "U301") (pin "13") (pinfunction "IO14_13") (pintype "bidirectional"))
    )
    (net (code "150") (name "SX1302_CSD") (class "Default")
      (node (ref "R105") (pin "2") (pinfunction "2_2") (pintype "bidirectional"))
      (node (ref "R207") (pin "1") (pinfunction "1_1") (pintype "bidirectional"))
      (node (ref "U101") (pin "10") (pinfunction "RADIO_CTRL_0/RADIO_A_LDO_EN_10") (pintype "bidirectional"))
    )
    (net (code "151") (name "SX1302_PA_ON") (class "Default")
      (node (ref "R209") (pin "1") (pinfunction "1_1") (pintype "bidirectional"))
      (node (ref "U101") (pin "16") (pinfunction "RADIO_CTRL_4/RADIO_A_PAGAIN_0_16") (pintype "bidirectional"))
    )
    (net (code "152") (name "SX1302_RXTX_SW") (class "Default")
      (node (ref "R208") (pin "1") (pinfunction "1_1") (pintype "bidirectional"))
      (node (ref "U101") (pin "12") (pinfunction "RADIO_CTRL_2/RADIO_A_PA_EN_12") (pintype "bidirectional"))
    )
    (net (code "153") (name "SX1302_VCC_CORE_1V2") (class "Default")
      (node (ref "C101") (pin "2") (pinfunction "2_2") (pintype "bidirectional"))
      (node (ref "C102") (pin "2") (pinfunction "2_2") (pintype "bidirectional"))
      (node (ref "C107") (pin "2") (pinfunction "2_2") (pintype "bidirectional"))
      (node (ref "C108") (pin "2") (pinfunction "2_2") (pintype "bidirectional"))
      (node (ref "C109") (pin "2") (pinfunction "2_2") (pintype "bidirectional"))
      (node (ref "C110") (pin "2") (pinfunction "2_2") (pintype "bidirectional"))
      (node (ref "C511") (pin "2") (pinfunction "2_2") (pintype "bidirectional"))
      (node (ref "FB502") (pin "2") (pinfunction "2_2") (pintype "bidirectional"))
      (node (ref "R501") (pin "1") (pinfunction "1_1") (pintype "bidirectional"))
      (node (ref "SX-VCC-CORE") (pin "1") (pinfunction "P$1_1") (pintype "bidirectional"))
      (node (ref "U101") (pin "23") (pinfunction "VCC_CORE_23") (pintype "bidirectional"))
      (node (ref "U101") (pin "40") (pinfunction "VCC_CORE_40") (pintype "bidirectional"))
      (node (ref "U101") (pin "5") (pinfunction "VCC_CORE_5") (pintype "bidirectional"))
      (node (ref "U101") (pin "56") (pinfunction "VCC_CORE_56") (pintype "bidirectional"))
    )
    (net (code "154") (name "TCXO_32M") (class "Default")
      (node (ref "R201") (pin "1") (pinfunction "1_1") (pintype "bidirectional"))
      (node (ref "R202") (pin "1") (pinfunction "1_1") (pintype "bidirectional"))
      (node (ref "R211") (pin "2") (pinfunction "2_2") (pintype "bidirectional"))
    )
    (net (code "155") (name "TCXO_VDD") (class "Default")
      (node (ref "C222") (pin "2") (pinfunction "2_2") (pintype "bidirectional"))
      (node (ref "FB203") (pin "2") (pinfunction "2_2") (pintype "bidirectional"))
      (node (ref "R212") (pin "2") (pinfunction "2_2") (pintype "bidirectional"))
      (node (ref "X201") (pin "4") (pinfunction "VDD_4") (pintype "bidirectional"))
    )
    (net (code "156") (name "TD_N") (class "Default")
      (node (ref "C412") (pin "2") (pinfunction "2_2") (pintype "bidirectional"))
      (node (ref "J401") (pin "2") (pinfunction "TD-_2") (pintype "bidirectional"))
      (node (ref "U401") (pin "29") (pinfunction "MDI_TN_29") (pintype "bidirectional"))
    )
    (net (code "157") (name "TD_P") (class "Default")
      (node (ref "C413") (pin "2") (pinfunction "2_2") (pintype "bidirectional"))
      (node (ref "J401") (pin "1") (pinfunction "TD+_1") (pintype "bidirectional"))
      (node (ref "U401") (pin "30") (pinfunction "MDI_TP_30") (pintype "bidirectional"))
    )
    (net (code "158") (name "TEMPSENS") (class "Default")
      (node (ref "C209") (pin "2") (pinfunction "2_2") (pintype "bidirectional"))
      (node (ref "R203") (pin "2") (pinfunction "2_2") (pintype "bidirectional"))
      (node (ref "RT201") (pin "2") (pinfunction "2_2") (pintype "bidirectional"))
      (node (ref "U301") (pin "5") (pinfunction "VN_5") (pintype "bidirectional"))
    )
    (net (code "159") (name "USB_N") (class "Default")
      (node (ref "SJ501") (pin "2") (pinfunction "2_2") (pintype "passive"))
      (node (ref "U601") (pin "6") (pinfunction "D-_6") (pintype "bidirectional"))
    )
    (net (code "160") (name "USB_P") (class "Default")
      (node (ref "SJ502") (pin "2") (pinfunction "2_2") (pintype "passive"))
      (node (ref "U601") (pin "5") (pinfunction "D+_5") (pintype "bidirectional"))
    )
    (net (code "161") (name "VBUS") (class "Default")
      (node (ref "F501") (pin "1") (pinfunction "1_1") (pintype "bidirectional"))
      (node (ref "J301") (pin "4") (pinfunction "4_4") (pintype "bidirectional"))
      (node (ref "J501") (pin "1") (pinfunction "VBUS_1") (pintype "bidirectional"))
    )
    (net (code "162") (name "VCC") (class "Default")
      (node (ref "C501") (pin "2") (pinfunction "2_2") (pintype "bidirectional"))
      (node (ref "C502") (pin "1") (pinfunction "1_1") (pintype "bidirectional"))
      (node (ref "C503") (pin "2") (pinfunction "2_2") (pintype "bidirectional"))
      (node (ref "F501") (pin "2") (pinfunction "2_2") (pintype "bidirectional"))
      (node (ref "U501") (pin "1") (pinfunction "EN/PG_1") (pintype "bidirectional"))
      (node (ref "U501") (pin "4") (pinfunction "VIN_4") (pintype "bidirectional"))
      (node (ref "U502") (pin "4") (pinfunction "VIN_4") (pintype "bidirectional"))
      (node (ref "U503") (pin "6") (pinfunction "VIN_6") (pintype "bidirectional"))
      (node (ref "VCC") (pin "1") (pinfunction "P$1_1") (pintype "bidirectional"))
    )
    (net (code "163") (name "VCC_TARGET_NC") (class "Default")
      (node (ref "J302") (pin "1") (pinfunction "VCC_1") (pintype "power_in"))
    )
    (net (code "164") (name "unconnected-(J401A-NC-Pad7)") (class "Default")
      (node (ref "J401") (pin "7") (pinfunction "NC_7") (pintype "passive"))
    )
    (net (code "165") (name "unconnected-(J501-ID-Pad4)") (class "Default")
      (node (ref "J501") (pin "4") (pinfunction "ID_4") (pintype "bidirectional"))
    )
    (net (code "166") (name "unconnected-(U101-GPIO_0-Pad66)") (class "Default")
      (node (ref "U101") (pin "66") (pinfunction "GPIO_0_66") (pintype "bidirectional"))
    )
    (net (code "167") (name "unconnected-(U101-GPIO_1-Pad64)") (class "Default")
      (node (ref "U101") (pin "64") (pinfunction "GPIO_1_64") (pintype "bidirectional"))
    )
    (net (code "168") (name "unconnected-(U101-GPIO_2-Pad63)") (class "Default")
      (node (ref "U101") (pin "63") (pinfunction "GPIO_2_63") (pintype "bidirectional"))
    )
    (net (code "169") (name "unconnected-(U101-GPIO_3-Pad60)") (class "Default")
      (node (ref "U101") (pin "60") (pinfunction "GPIO_3_60") (pintype "bidirectional"))
    )
    (net (code "170") (name "unconnected-(U101-GPIO_4-Pad59)") (class "Default")
      (node (ref "U101") (pin "59") (pinfunction "GPIO_4_59") (pintype "bidirectional"))
    )
    (net (code "171") (name "unconnected-(U101-GPIO_5-Pad58)") (class "Default")
      (node (ref "U101") (pin "58") (pinfunction "GPIO_5_58") (pintype "bidirectional"))
    )
    (net (code "172") (name "unconnected-(U101-GPIO_6-Pad57)") (class "Default")
      (node (ref "U101") (pin "57") (pinfunction "GPIO_6_57") (pintype "bidirectional"))
    )
    (net (code "173") (name "unconnected-(U101-GPIO_8-Pad53)") (class "Default")
      (node (ref "U101") (pin "53") (pinfunction "GPIO_8_53") (pintype "bidirectional"))
    )
    (net (code "174") (name "unconnected-(U101-GPIO_9-Pad52)") (class "Default")
      (node (ref "U101") (pin "52") (pinfunction "GPIO_9_52") (pintype "bidirectional"))
    )
    (net (code "175") (name "unconnected-(U101-GPIO_10-Pad51)") (class "Default")
      (node (ref "U101") (pin "51") (pinfunction "GPIO_10_51") (pintype "bidirectional"))
    )
    (net (code "176") (name "unconnected-(U101-GPIO_11-Pad50)") (class "Default")
      (node (ref "U101") (pin "50") (pinfunction "GPIO_11_50") (pintype "bidirectional"))
    )
    (net (code "177") (name "unconnected-(U101-RADIO_CTRL_1{slash}RADIO_A_LNA_EN-Pad11)") (class "Default")
      (node (ref "U101") (pin "11") (pinfunction "RADIO_CTRL_1/RADIO_A_LNA_EN_11") (pintype "bidirectional"))
    )
    (net (code "178") (name "unconnected-(U101-RADIO_CTRL_5{slash}RADIO_A_PAGAIN_1-Pad17)") (class "Default")
      (node (ref "U101") (pin "17") (pinfunction "RADIO_CTRL_5/RADIO_A_PAGAIN_1_17") (pintype "bidirectional"))
    )
    (net (code "179") (name "unconnected-(U101-RADIO_CTRL_6{slash}RADIO_B_LDO_EN-Pad22)") (class "Default")
      (node (ref "U101") (pin "22") (pinfunction "RADIO_CTRL_6/RADIO_B_LDO_EN_22") (pintype "bidirectional"))
    )
    (net (code "180") (name "unconnected-(U101-RADIO_CTRL_7{slash}RADIO_B_LNA_EN-Pad26)") (class "Default")
      (node (ref "U101") (pin "26") (pinfunction "RADIO_CTRL_7/RADIO_B_LNA_EN_26") (pintype "bidirectional"))
    )
    (net (code "181") (name "unconnected-(U101-RADIO_CTRL_8{slash}RADIO_B_PA_EN-Pad27)") (class "Default")
      (node (ref "U101") (pin "27") (pinfunction "RADIO_CTRL_8/RADIO_B_PA_EN_27") (pintype "bidirectional"))
    )
    (net (code "182") (name "unconnected-(U101-RADIO_CTRL_10{slash}RADIO_B_PAGAIN_0-Pad29)") (class "Default")
      (node (ref "U101") (pin "29") (pinfunction "RADIO_CTRL_10/RADIO_B_PAGAIN_0_29") (pintype "bidirectional"))
    )
    (net (code "183") (name "unconnected-(U101-RADIO_CTRL_11{slash}RADIO_B_PAGAIN_1-Pad31)") (class "Default")
      (node (ref "U101") (pin "31") (pinfunction "RADIO_CTRL_11/RADIO_B_PAGAIN_1_31") (pintype "bidirectional"))
    )
    (net (code "184") (name "unconnected-(U201-XTB-Pad4)") (class "Default")
      (node (ref "U201") (pin "4") (pinfunction "XTB_4") (pintype "bidirectional"))
    )
    (net (code "185") (name "unconnected-(U202-RFO-Pad24)") (class "Default")
      (node (ref "U202") (pin "24") (pinfunction "RFO_24") (pintype "bidirectional"))
    )
    (net (code "186") (name "unconnected-(U202-VR_PA-Pad1)") (class "Default")
      (node (ref "U202") (pin "1") (pinfunction "VR_PA_1") (pintype "bidirectional"))
    )
    (net (code "187") (name "unconnected-(U202-XTB-Pad4)") (class "Default")
      (node (ref "U202") (pin "4") (pinfunction "XTB_4") (pintype "bidirectional"))
    )
    (net (code "188") (name "unconnected-(U205-TX_ALT-Pad3)") (class "Default")
      (node (ref "U205") (pin "3") (pinfunction "TX_ALT_3") (pintype "bidirectional"))
    )
    (net (code "189") (name "unconnected-(U301-CLK-Pad20)") (class "Default")
      (node (ref "U301") (pin "20") (pinfunction "CLK_20") (pintype "bidirectional"))
    )
    (net (code "190") (name "unconnected-(U301-CMD-Pad19)") (class "Default")
      (node (ref "U301") (pin "19") (pinfunction "CMD_19") (pintype "bidirectional"))
    )
    (net (code "191") (name "unconnected-(U301-IO34-Pad6)") (class "Default")
      (node (ref "U301") (pin "6") (pinfunction "IO34_6") (pintype "bidirectional"))
    )
    (net (code "192") (name "unconnected-(U301-NC-Pad32)") (class "Default")
      (node (ref "U301") (pin "32") (pinfunction "NC_32") (pintype "bidirectional"))
    )
    (net (code "193") (name "unconnected-(U301-SD0-Pad21)") (class "Default")
      (node (ref "U301") (pin "21") (pinfunction "SD0_21") (pintype "bidirectional"))
    )
    (net (code "194") (name "unconnected-(U301-SD1-Pad22)") (class "Default")
      (node (ref "U301") (pin "22") (pinfunction "SD1_22") (pintype "bidirectional"))
    )
    (net (code "195") (name "unconnected-(U301-SD2-Pad17)") (class "Default")
      (node (ref "U301") (pin "17") (pinfunction "SD2_17") (pintype "bidirectional"))
    )
    (net (code "196") (name "unconnected-(U301-SD3-Pad18)") (class "Default")
      (node (ref "U301") (pin "18") (pinfunction "SD3_18") (pintype "bidirectional"))
    )
    (net (code "197") (name "unconnected-(U301-VP-Pad4)") (class "Default")
      (node (ref "U301") (pin "4") (pinfunction "VP_4") (pintype "bidirectional"))
    )
    (net (code "198") (name "unconnected-(U401-RXD2-Pad16)") (class "Default")
      (node (ref "U401") (pin "16") (pinfunction "RXD2_16") (pintype "bidirectional"))
    )
    (net (code "199") (name "unconnected-(U401-RXD3-Pad15)") (class "Default")
      (node (ref "U401") (pin "15") (pinfunction "RXD3_15") (pintype "bidirectional"))
    )
    (net (code "200") (name "unconnected-(U401-TXD2-Pad7)") (class "Default")
      (node (ref "U401") (pin "7") (pinfunction "TXD2_7") (pintype "bidirectional"))
    )
    (net (code "201") (name "unconnected-(U401-TXD3-Pad6)") (class "Default")
      (node (ref "U401") (pin "6") (pinfunction "TXD3_6") (pintype "bidirectional"))
    )
    (net (code "202") (name "unconnected-(U601-CTS#-Pad9)") (class "Default")
      (node (ref "U601") (pin "9") (pinfunction "CTS#_9") (pintype "bidirectional"))
    )
    (net (code "203") (name "unconnected-(U601-DCD#-Pad12)") (class "Default")
      (node (ref "U601") (pin "12") (pinfunction "DCD#_12") (pintype "bidirectional"))
    )
    (net (code "204") (name "unconnected-(U601-DSR#-Pad10)") (class "Default")
      (node (ref "U601") (pin "10") (pinfunction "DSR#_10") (pintype "bidirectional"))
    )
    (net (code "205") (name "unconnected-(U601-NC-Pad7)") (class "Default")
      (node (ref "U601") (pin "7") (pinfunction "NC_7") (pintype "bidirectional"))
    )
    (net (code "206") (name "unconnected-(U601-NC.-Pad8)") (class "Default")
      (node (ref "U601") (pin "8") (pinfunction "NC._8") (pintype "bidirectional"))
    )
    (net (code "207") (name "unconnected-(U601-RI#-Pad11)") (class "Default")
      (node (ref "U601") (pin "11") (pinfunction "RI#_11") (pintype "bidirectional"))
    )
    (net (code "208") (name "unconnected-(U601-RS232-Pad15)") (class "Default")
      (node (ref "U601") (pin "15") (pinfunction "RS232_15") (pintype "bidirectional"))
    )
    (net (code "209") (name "~{ESP_RST}") (class "Default")
      (node (ref "ESP-!RST!") (pin "1") (pinfunction "P$1_1") (pintype "bidirectional"))
      (node (ref "J302") (pin "3") (pinfunction "RST_3") (pintype "bidirectional"))
      (node (ref "Q602") (pin "3") (pinfunction "C_3") (pintype "passive"))
      (node (ref "R301") (pin "2") (pinfunction "2_2") (pintype "bidirectional"))
      (node (ref "U301") (pin "3") (pinfunction "EN_3") (pintype "bidirectional"))
    )
    (net (code "210") (name "~{PHY_RST}") (class "Default")
      (node (ref "!PHY-RST!") (pin "1") (pinfunction "P$1_1") (pintype "bidirectional"))
      (node (ref "C401") (pin "2") (pinfunction "2_2") (pintype "bidirectional"))
      (node (ref "R401") (pin "2") (pinfunction "2_2") (pintype "bidirectional"))
      (node (ref "U301") (pin "24") (pinfunction "IO2_24") (pintype "bidirectional"))
      (node (ref "U401") (pin "32") (pinfunction "~{RESET}_32") (pintype "bidirectional"))
    )
    (net (code "211") (name "~{RADIO_A_CS}") (class "Default")
      (node (ref "U101") (pin "68") (pinfunction "~{RADIO_A_CS}_68") (pintype "bidirectional"))
      (node (ref "U201") (pin "19") (pinfunction "~{SS}_19") (pintype "input"))
    )
    (net (code "212") (name "~{RADIO_A_RST}") (class "Default")
      (node (ref "U101") (pin "13") (pinfunction "RADIO_CTRL_3/RADIO_A_RESET_13") (pintype "bidirectional"))
      (node (ref "U201") (pin "15") (pinfunction "~{RST}_15") (pintype "input"))
    )
    (net (code "213") (name "~{RADIO_B_CS}") (class "Default")
      (node (ref "U101") (pin "18") (pinfunction "~{RADIO_B_CS}_18") (pintype "bidirectional"))
      (node (ref "U202") (pin "19") (pinfunction "~{SS}_19") (pintype "input"))
    )
    (net (code "214") (name "~{RADIO_B_RST}") (class "Default")
      (node (ref "U101") (pin "28") (pinfunction "RADIO_CTRL_9/RADIO_B_RESET_28") (pintype "bidirectional"))
      (node (ref "U202") (pin "15") (pinfunction "~{RST}_15") (pintype "input"))
    )
    (net (code "215") (name "~{SPI_CS0}") (class "Default")
      (node (ref "R104") (pin "2") (pinfunction "2_2") (pintype "bidirectional"))
      (node (ref "SX-!CS!") (pin "1") (pinfunction "P$1_1") (pintype "bidirectional"))
      (node (ref "U101") (pin "1") (pinfunction "~{HOST_CS}_1") (pintype "bidirectional"))
      (node (ref "U301") (pin "23") (pinfunction "IO15_23") (pintype "bidirectional"))
    )
    (net (code "216") (name "~{SX1302_RST}") (class "Default")
      (node (ref "R101") (pin "2") (pinfunction "2_2") (pintype "bidirectional"))
      (node (ref "SX-!RST!") (pin "1") (pinfunction "P$1_1") (pintype "bidirectional"))
      (node (ref "U101") (pin "7") (pinfunction "~{RESET}_7") (pintype "bidirectional"))
      (node (ref "U301") (pin "26") (pinfunction "IO4_26") (pintype "bidirectional"))
    )
  )
)
